# MOSFET_Board.net
KiCad netlist of a schematic drawn in EAGLE
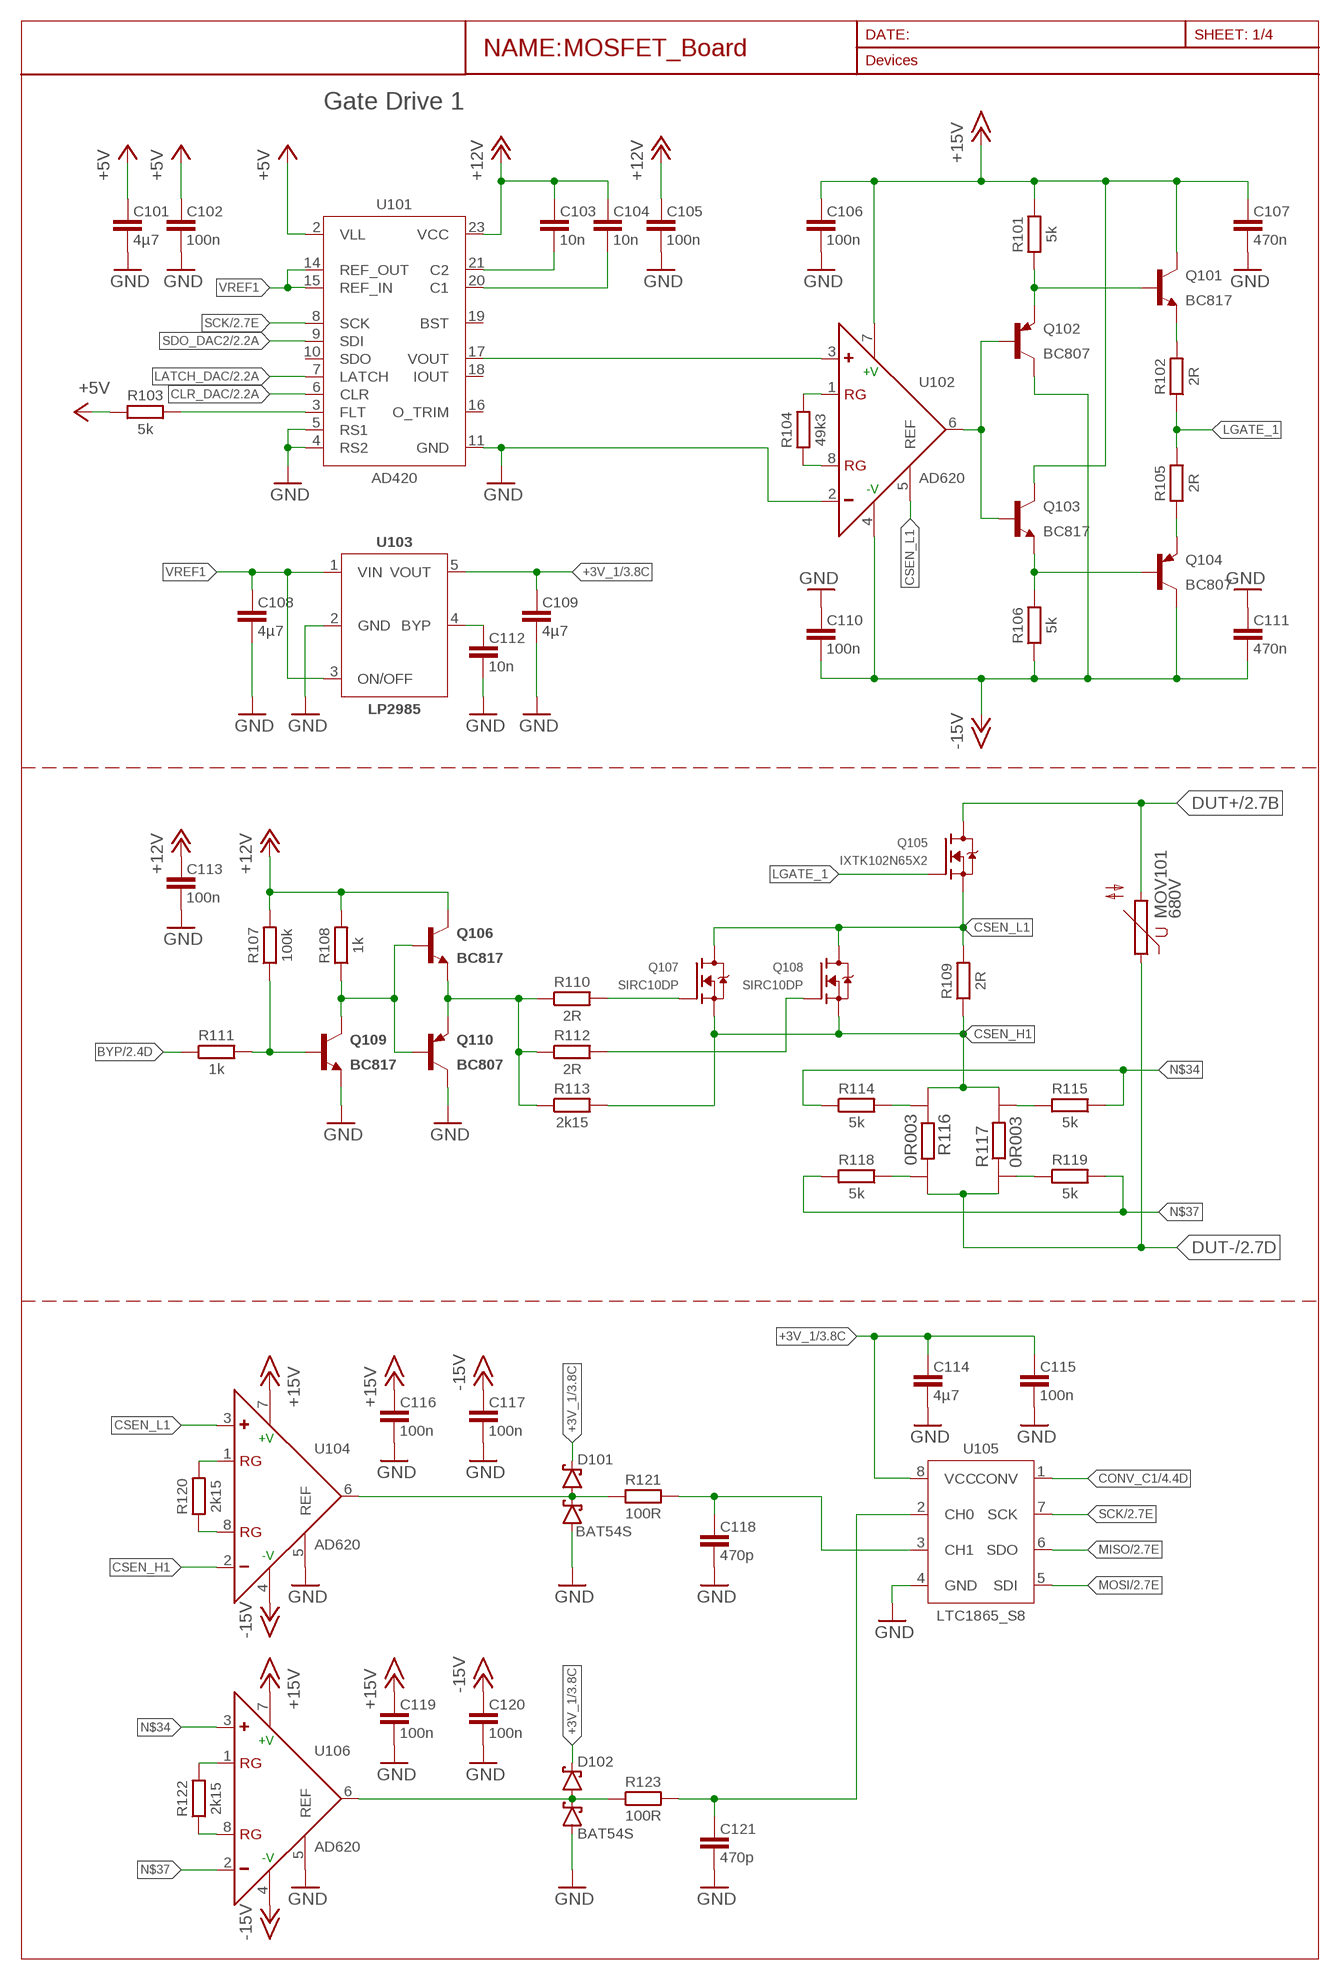
[diagram p0: schematic, sheet 1]
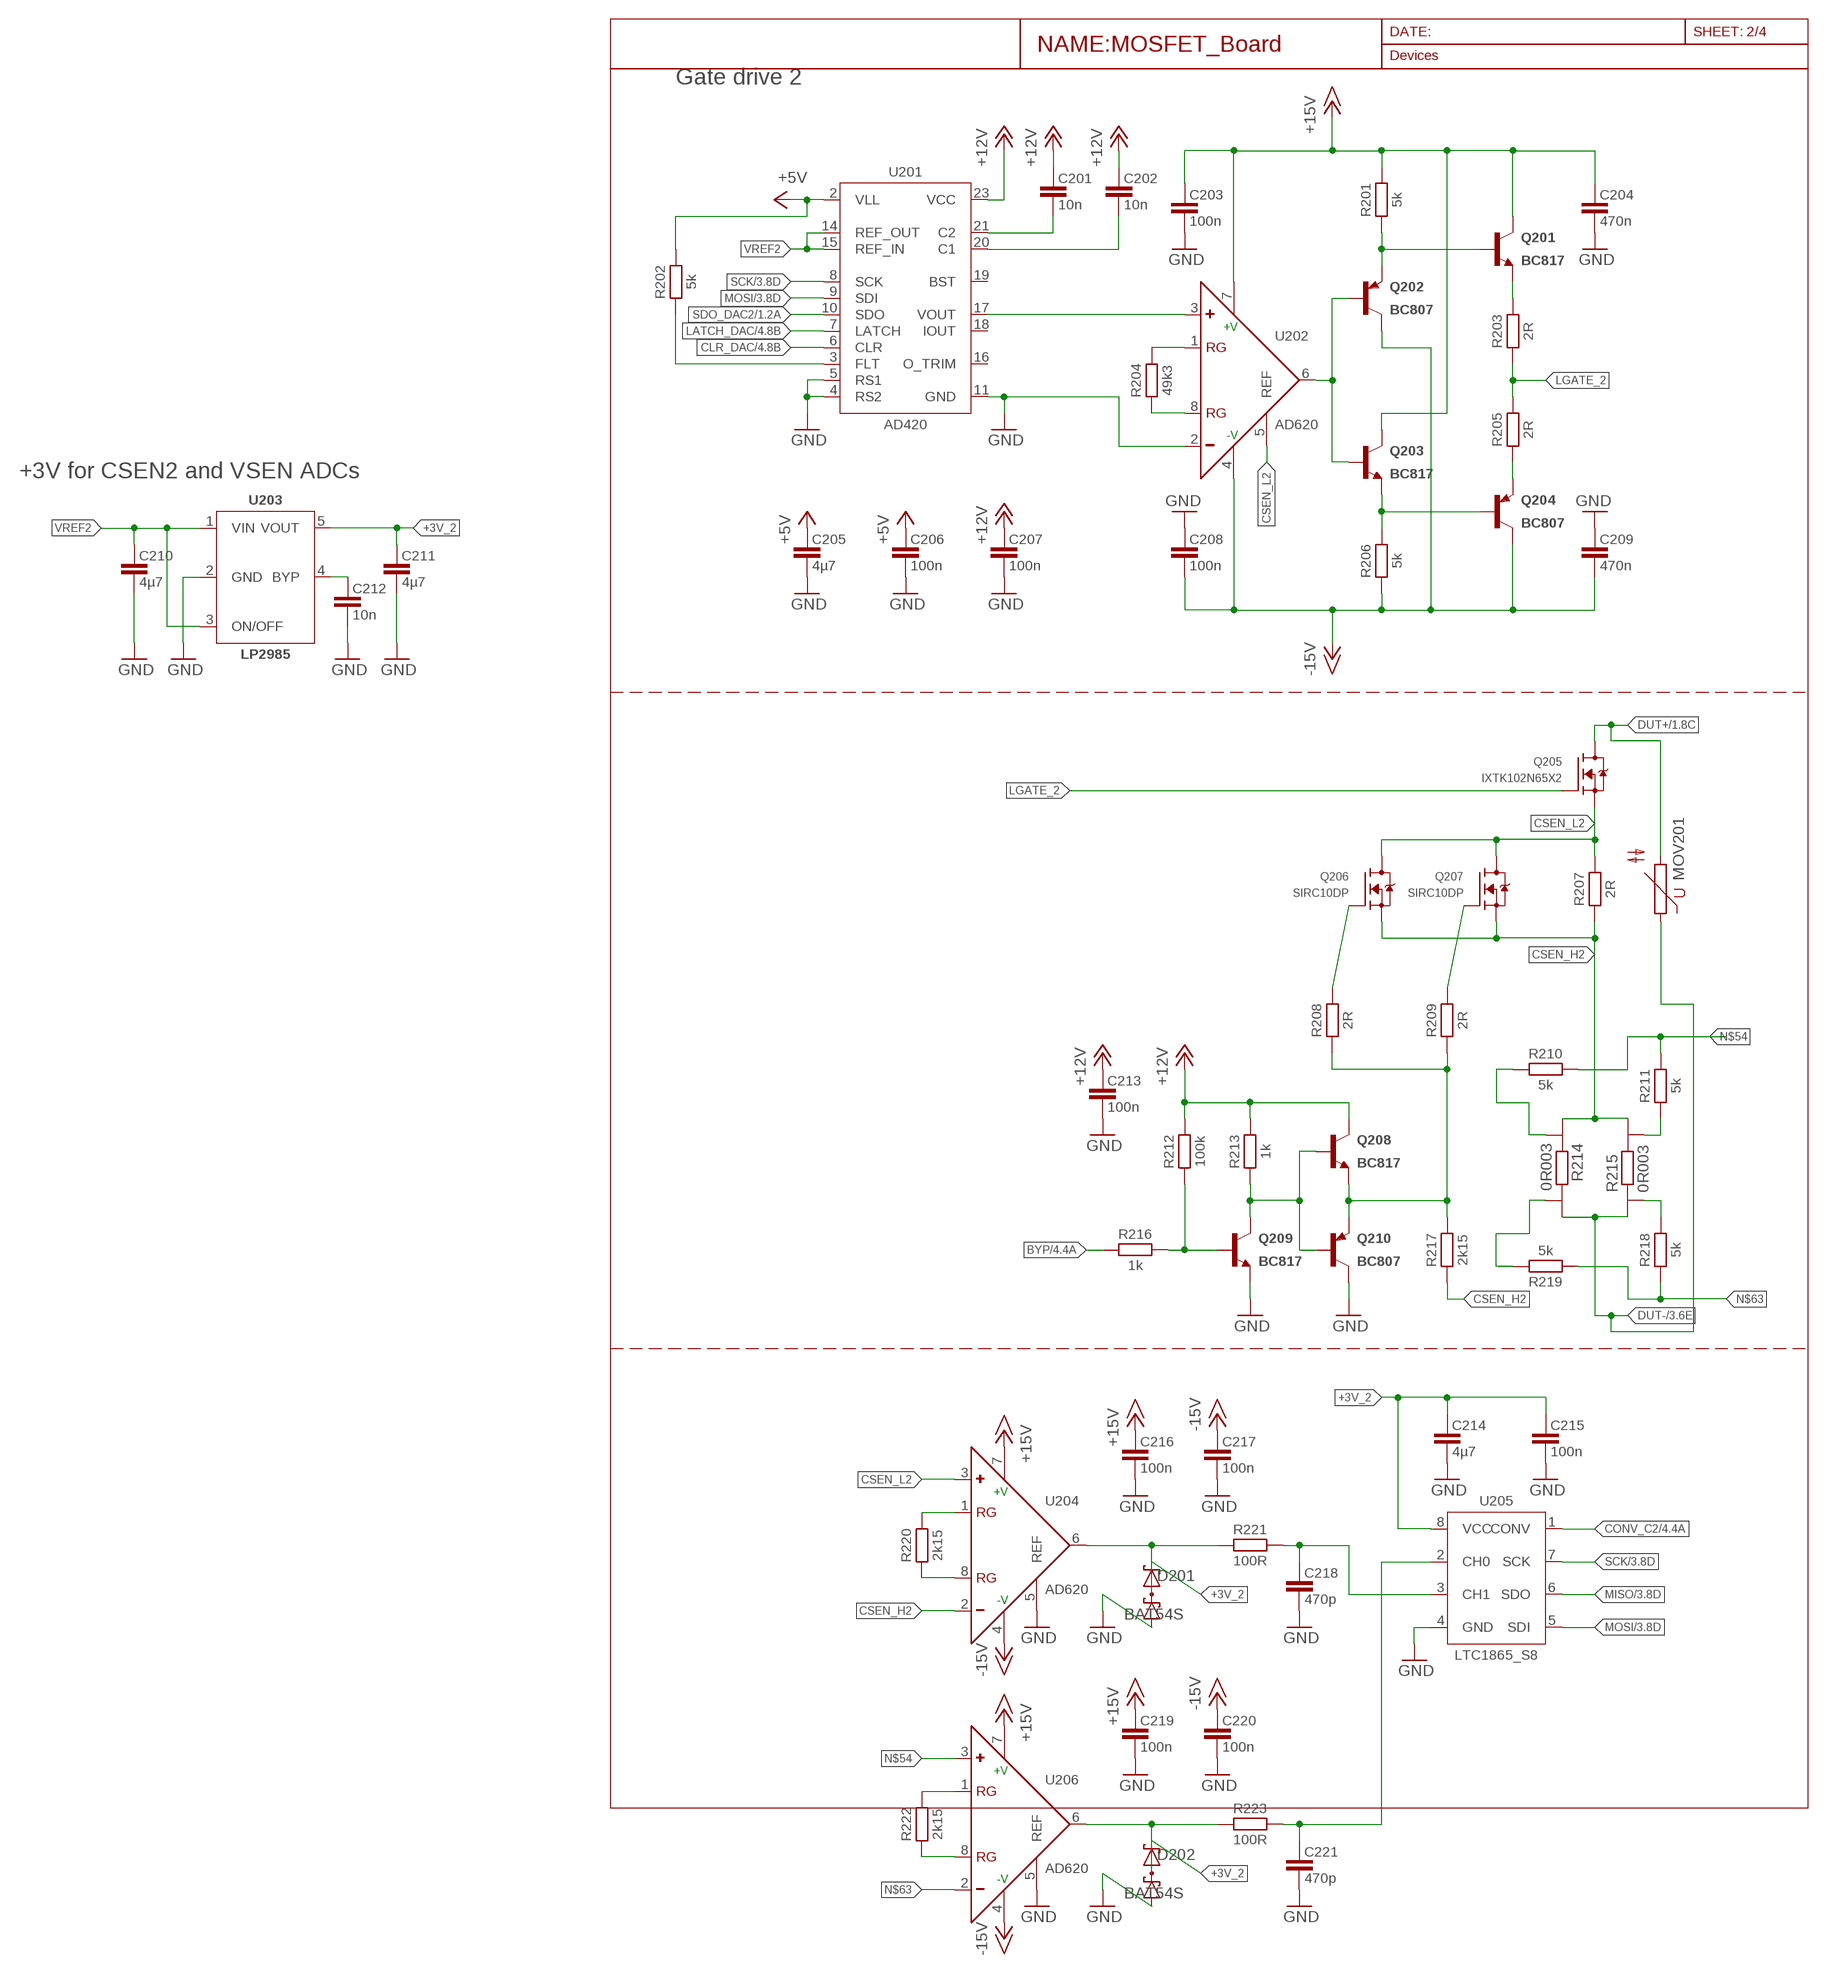
[diagram p1: schematic, sheet 2]
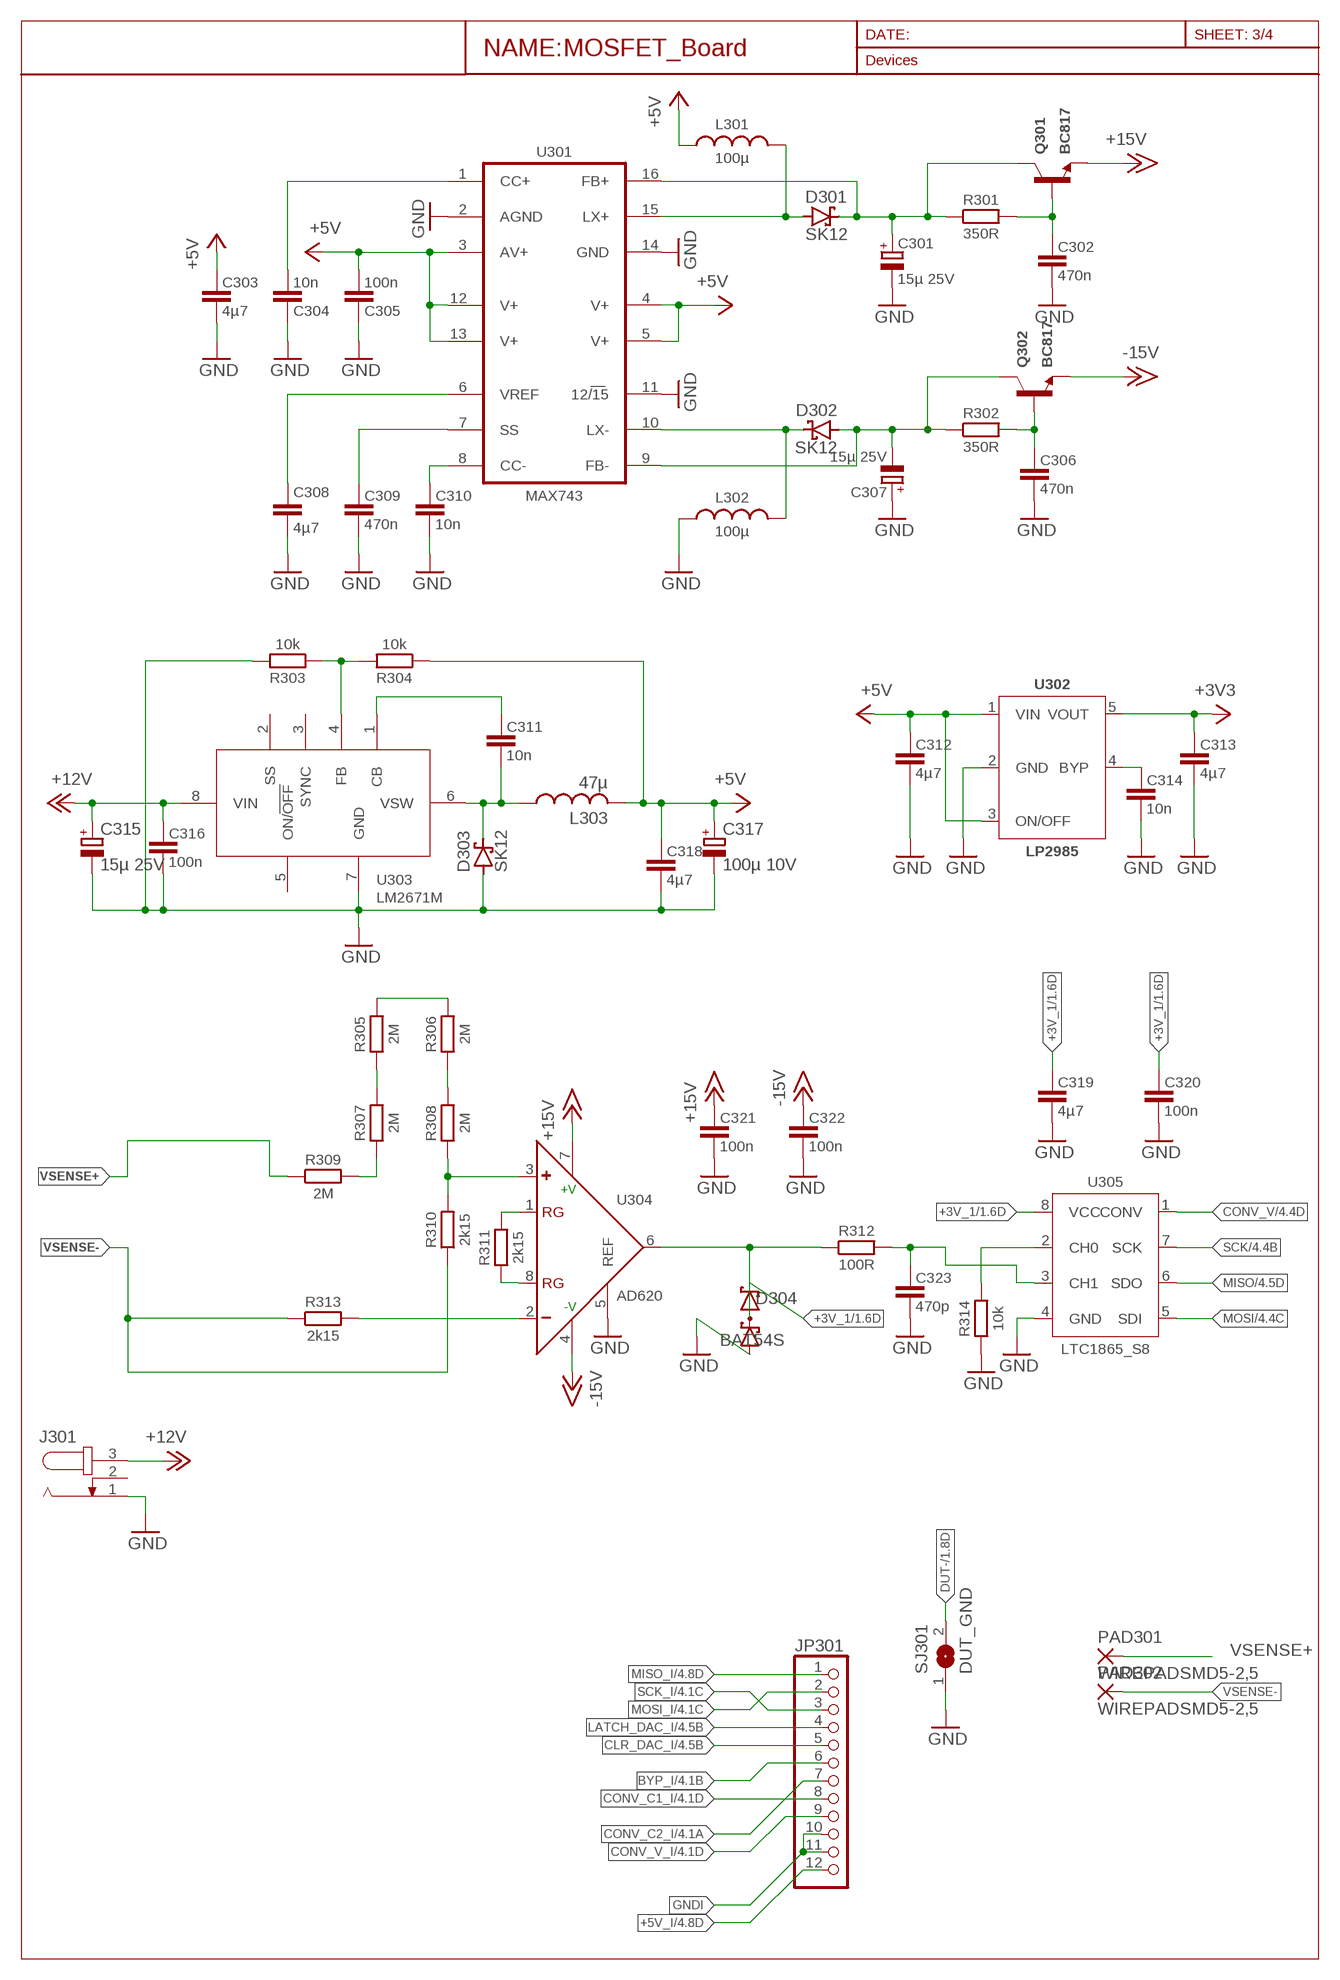
[diagram p2: schematic, sheet 3]
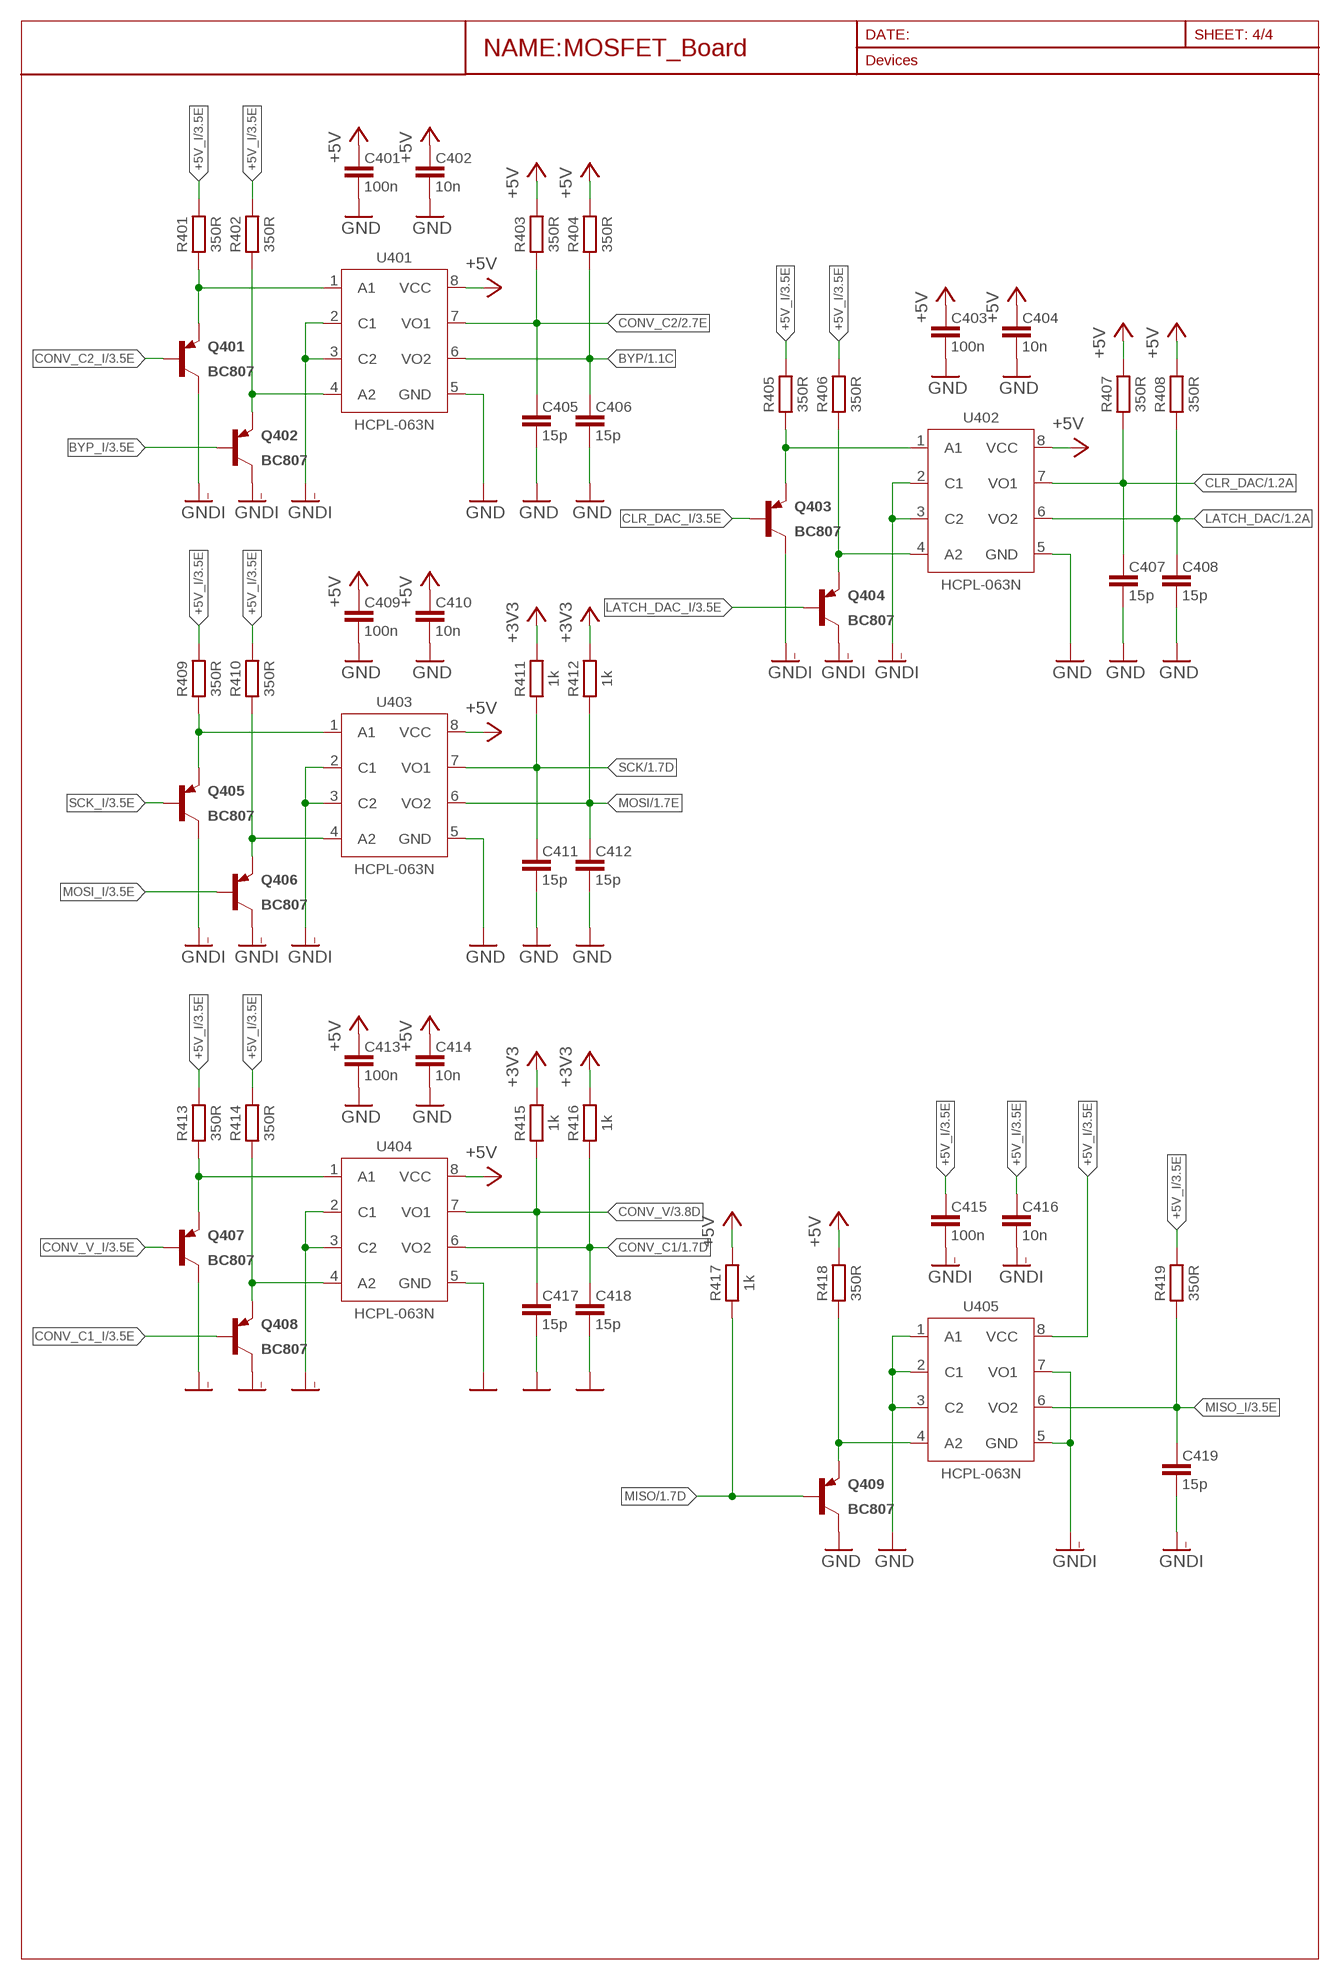
[diagram p3: schematic, sheet 4]

(export (version "E")
  (design (tool "Eeschema 10.0.6"))
  (components
    (comp (ref "C201")
      (value "10n")
      (footprint "eagle-import:CAPC1508X45")
      (libsource (lib "eagle-import") (part "CAP-1608"))
    )
    (comp (ref "C202")
      (value "10n")
      (footprint "eagle-import:CAPC1508X45")
      (libsource (lib "eagle-import") (part "CAP-1608"))
    )
    (comp (ref "C203")
      (value "100n")
      (footprint "eagle-import:CAPC1508X45")
      (libsource (lib "eagle-import") (part "CAP-1608"))
    )
    (comp (ref "C204")
      (value "470n")
      (footprint "eagle-import:CAPC1508X45")
      (libsource (lib "eagle-import") (part "CAP-1608"))
    )
    (comp (ref "C205")
      (value "4µ7")
      (footprint "eagle-import:CAPC3216X135")
      (libsource (lib "eagle-import") (part "CAP-3216"))
    )
    (comp (ref "C206")
      (value "100n")
      (footprint "eagle-import:CAPC1508X45")
      (libsource (lib "eagle-import") (part "CAP-1608"))
    )
    (comp (ref "C207")
      (value "100n")
      (footprint "eagle-import:CAPC1508X45")
      (libsource (lib "eagle-import") (part "CAP-1608"))
    )
    (comp (ref "C208")
      (value "100n")
      (footprint "eagle-import:CAPC1508X45")
      (libsource (lib "eagle-import") (part "CAP-1608"))
    )
    (comp (ref "C209")
      (value "470n")
      (footprint "eagle-import:CAPC1508X45")
      (libsource (lib "eagle-import") (part "CAP-1608"))
    )
    (comp (ref "C210")
      (value "4µ7")
      (footprint "eagle-import:CAPC3216X135")
      (libsource (lib "eagle-import") (part "CAP-3216"))
    )
    (comp (ref "C211")
      (value "4µ7")
      (footprint "eagle-import:CAPC3216X135")
      (libsource (lib "eagle-import") (part "CAP-3216"))
    )
    (comp (ref "C212")
      (value "10n")
      (footprint "eagle-import:CAPC1508X45")
      (libsource (lib "eagle-import") (part "CAP-1608"))
    )
    (comp (ref "C213")
      (value "100n")
      (footprint "eagle-import:CAPC1508X45")
      (libsource (lib "eagle-import") (part "CAP-1608"))
    )
    (comp (ref "C214")
      (value "4µ7")
      (footprint "eagle-import:CAPC3216X135")
      (libsource (lib "eagle-import") (part "CAP-3216"))
    )
    (comp (ref "C215")
      (value "100n")
      (footprint "eagle-import:CAPC1508X45")
      (libsource (lib "eagle-import") (part "CAP-1608"))
    )
    (comp (ref "C216")
      (value "100n")
      (footprint "eagle-import:CAPC1508X45")
      (libsource (lib "eagle-import") (part "CAP-1608"))
    )
    (comp (ref "C217")
      (value "100n")
      (footprint "eagle-import:CAPC1508X45")
      (libsource (lib "eagle-import") (part "CAP-1608"))
    )
    (comp (ref "C218")
      (value "470p")
      (footprint "eagle-import:CAPC1508X45")
      (libsource (lib "eagle-import") (part "CAP-1608"))
    )
    (comp (ref "C219")
      (value "100n")
      (footprint "eagle-import:CAPC1508X45")
      (libsource (lib "eagle-import") (part "CAP-1608"))
    )
    (comp (ref "C220")
      (value "100n")
      (footprint "eagle-import:CAPC1508X45")
      (libsource (lib "eagle-import") (part "CAP-1608"))
    )
    (comp (ref "C221")
      (value "470p")
      (footprint "eagle-import:CAPC1508X45")
      (libsource (lib "eagle-import") (part "CAP-1608"))
    )
    (comp (ref "D201")
      (value "BAT54S")
      (footprint "eagle-import:SOT95P230X110-3")
      (libsource (lib "eagle-import") (part "BAT54S"))
    )
    (comp (ref "D202")
      (value "BAT54S")
      (footprint "eagle-import:SOT95P230X110-3")
      (libsource (lib "eagle-import") (part "BAT54S"))
    )
    (comp (ref "MOV201")
      (value "MOV-14X7.4")
      (footprint "eagle-import:S14K680")
      (libsource (lib "eagle-import") (part "MOV-14X7.4"))
    )
    (comp (ref "Q201")
      (value "BC817")
      (footprint "eagle-import:SOT95P240X110-3")
      (libsource (lib "eagle-import") (part "BC817"))
    )
    (comp (ref "Q202")
      (value "BC807")
      (footprint "eagle-import:SOT95P240X110-3")
      (libsource (lib "eagle-import") (part "BC807"))
    )
    (comp (ref "Q203")
      (value "BC817")
      (footprint "eagle-import:SOT95P240X110-3")
      (libsource (lib "eagle-import") (part "BC817"))
    )
    (comp (ref "Q204")
      (value "BC807")
      (footprint "eagle-import:SOT95P240X110-3")
      (libsource (lib "eagle-import") (part "BC807"))
    )
    (comp (ref "Q205")
      (value "IXTK102N65X2")
      (footprint "eagle-import:TO-264P-V")
      (libsource (lib "eagle-import") (part "IXTK102N65X2"))
    )
    (comp (ref "Q206")
      (value "SIRC10DP")
      (footprint "eagle-import:POWERPAK-SO-8")
      (libsource (lib "eagle-import") (part "SIRC10DP"))
    )
    (comp (ref "Q207")
      (value "SIRC10DP")
      (footprint "eagle-import:POWERPAK-SO-8")
      (libsource (lib "eagle-import") (part "SIRC10DP"))
    )
    (comp (ref "Q208")
      (value "BC817")
      (footprint "eagle-import:SOT95P240X110-3")
      (libsource (lib "eagle-import") (part "BC817"))
    )
    (comp (ref "Q209")
      (value "BC817")
      (footprint "eagle-import:SOT95P240X110-3")
      (libsource (lib "eagle-import") (part "BC817"))
    )
    (comp (ref "Q210")
      (value "BC807")
      (footprint "eagle-import:SOT95P240X110-3")
      (libsource (lib "eagle-import") (part "BC807"))
    )
    (comp (ref "R201")
      (value "5k")
      (footprint "eagle-import:RESC1608X70")
      (libsource (lib "eagle-import") (part "R-EU-1608"))
    )
    (comp (ref "R202")
      (value "5k")
      (footprint "eagle-import:RESC1608X70")
      (libsource (lib "eagle-import") (part "R-EU-1608"))
    )
    (comp (ref "R203")
      (value "2R")
      (footprint "eagle-import:RESC3216X71")
      (libsource (lib "eagle-import") (part "R-EU-3216"))
    )
    (comp (ref "R204")
      (value "49k3")
      (footprint "eagle-import:RESC1608X70")
      (libsource (lib "eagle-import") (part "R-EU-1608"))
    )
    (comp (ref "R205")
      (value "2R")
      (footprint "eagle-import:RESC3216X71")
      (libsource (lib "eagle-import") (part "R-EU-3216"))
    )
    (comp (ref "R206")
      (value "5k")
      (footprint "eagle-import:RESC1608X70")
      (libsource (lib "eagle-import") (part "R-EU-1608"))
    )
    (comp (ref "R207")
      (value "2R")
      (footprint "eagle-import:RESC3216X71")
      (libsource (lib "eagle-import") (part "R-EU-3216"))
    )
    (comp (ref "R208")
      (value "2R")
      (footprint "eagle-import:RESC3216X71")
      (libsource (lib "eagle-import") (part "R-EU-3216"))
    )
    (comp (ref "R209")
      (value "2R")
      (footprint "eagle-import:RESC3216X71")
      (libsource (lib "eagle-import") (part "R-EU-3216"))
    )
    (comp (ref "R210")
      (value "5k")
      (footprint "eagle-import:RESC1608X70")
      (libsource (lib "eagle-import") (part "R-EU-1608"))
    )
    (comp (ref "R211")
      (value "5k")
      (footprint "eagle-import:RESC1608X70")
      (libsource (lib "eagle-import") (part "R-EU-1608"))
    )
    (comp (ref "R212")
      (value "100k")
      (footprint "eagle-import:RESC1608X70")
      (libsource (lib "eagle-import") (part "R-EU-1608"))
    )
    (comp (ref "R213")
      (value "1k")
      (footprint "eagle-import:RESC1608X70")
      (libsource (lib "eagle-import") (part "R-EU-1608"))
    )
    (comp (ref "R214")
      (value "0R003")
      (footprint "eagle-import:WSL3637_0.01")
      (libsource (lib "eagle-import") (part "WSL3637_0.01"))
    )
    (comp (ref "R215")
      (value "0R003")
      (footprint "eagle-import:WSL3637_0.01")
      (libsource (lib "eagle-import") (part "WSL3637_0.01"))
    )
    (comp (ref "R216")
      (value "1k")
      (footprint "eagle-import:RESC1608X70")
      (libsource (lib "eagle-import") (part "R-EU-1608"))
    )
    (comp (ref "R217")
      (value "2k15")
      (footprint "eagle-import:RESC2012X65")
      (libsource (lib "eagle-import") (part "R-EU-2012"))
    )
    (comp (ref "R218")
      (value "5k")
      (footprint "eagle-import:RESC1608X70")
      (libsource (lib "eagle-import") (part "R-EU-1608"))
    )
    (comp (ref "R219")
      (value "5k")
      (footprint "eagle-import:RESC1608X70")
      (libsource (lib "eagle-import") (part "R-EU-1608"))
    )
    (comp (ref "R220")
      (value "2k15")
      (footprint "eagle-import:RESC2012X65")
      (libsource (lib "eagle-import") (part "R-EU-2012"))
    )
    (comp (ref "R221")
      (value "100R")
      (footprint "eagle-import:RESC1608X70")
      (libsource (lib "eagle-import") (part "R-EU-1608"))
    )
    (comp (ref "R222")
      (value "2k15")
      (footprint "eagle-import:RESC2012X65")
      (libsource (lib "eagle-import") (part "R-EU-2012"))
    )
    (comp (ref "R223")
      (value "100R")
      (footprint "eagle-import:RESC1608X70")
      (libsource (lib "eagle-import") (part "R-EU-1608"))
    )
    (comp (ref "U201")
      (value "AD420")
      (footprint "eagle-import:SOIC127P1032X265-24")
      (libsource (lib "eagle-import") (part "AD420AR"))
    )
    (comp (ref "U202")
      (value "AD620")
      (footprint "eagle-import:SOIC127P599X175-8")
      (libsource (lib "eagle-import") (part "AD620R-8"))
    )
    (comp (ref "U203")
      (value "LP2985")
      (footprint "eagle-import:SOT95P280X145-5")
      (libsource (lib "eagle-import") (part "LP2985"))
    )
    (comp (ref "U204")
      (value "AD620")
      (footprint "eagle-import:SOIC127P599X175-8")
      (libsource (lib "eagle-import") (part "AD620R-8"))
    )
    (comp (ref "U205")
      (value "LTC1865_S8")
      (footprint "eagle-import:SOIC127P599X175-8")
      (libsource (lib "eagle-import") (part "LTC1865_S8"))
    )
    (comp (ref "U206")
      (value "AD620")
      (footprint "eagle-import:SOIC127P599X175-8")
      (libsource (lib "eagle-import") (part "AD620R-8"))
    )
    (comp (ref "C101")
      (value "4µ7")
      (footprint "eagle-import:CAPC3216X135")
      (libsource (lib "eagle-import") (part "CAP-3216"))
    )
    (comp (ref "C102")
      (value "100n")
      (footprint "eagle-import:CAPC1508X45")
      (libsource (lib "eagle-import") (part "CAP-1608"))
    )
    (comp (ref "C103")
      (value "10n")
      (footprint "eagle-import:CAPC1508X45")
      (libsource (lib "eagle-import") (part "CAP-1608"))
    )
    (comp (ref "C104")
      (value "10n")
      (footprint "eagle-import:CAPC1508X45")
      (libsource (lib "eagle-import") (part "CAP-1608"))
    )
    (comp (ref "C105")
      (value "100n")
      (footprint "eagle-import:CAPC1508X45")
      (libsource (lib "eagle-import") (part "CAP-1608"))
    )
    (comp (ref "C106")
      (value "100n")
      (footprint "eagle-import:CAPC1508X45")
      (libsource (lib "eagle-import") (part "CAP-1608"))
    )
    (comp (ref "C107")
      (value "470n")
      (footprint "eagle-import:CAPC1508X45")
      (libsource (lib "eagle-import") (part "CAP-1608"))
    )
    (comp (ref "C108")
      (value "4µ7")
      (footprint "eagle-import:CAPC3216X135")
      (libsource (lib "eagle-import") (part "CAP-3216"))
    )
    (comp (ref "C109")
      (value "4µ7")
      (footprint "eagle-import:CAPC3216X135")
      (libsource (lib "eagle-import") (part "CAP-3216"))
    )
    (comp (ref "C110")
      (value "100n")
      (footprint "eagle-import:CAPC1508X45")
      (libsource (lib "eagle-import") (part "CAP-1608"))
    )
    (comp (ref "C111")
      (value "470n")
      (footprint "eagle-import:CAPC1508X45")
      (libsource (lib "eagle-import") (part "CAP-1608"))
    )
    (comp (ref "C112")
      (value "10n")
      (footprint "eagle-import:CAPC1508X45")
      (libsource (lib "eagle-import") (part "CAP-1608"))
    )
    (comp (ref "C113")
      (value "100n")
      (footprint "eagle-import:CAPC1508X45")
      (libsource (lib "eagle-import") (part "CAP-1608"))
    )
    (comp (ref "C114")
      (value "4µ7")
      (footprint "eagle-import:CAPC3216X135")
      (libsource (lib "eagle-import") (part "CAP-3216"))
    )
    (comp (ref "C115")
      (value "100n")
      (footprint "eagle-import:CAPC1508X45")
      (libsource (lib "eagle-import") (part "CAP-1608"))
    )
    (comp (ref "C116")
      (value "100n")
      (footprint "eagle-import:CAPC1508X45")
      (libsource (lib "eagle-import") (part "CAP-1608"))
    )
    (comp (ref "C117")
      (value "100n")
      (footprint "eagle-import:CAPC1508X45")
      (libsource (lib "eagle-import") (part "CAP-1608"))
    )
    (comp (ref "C118")
      (value "470p")
      (footprint "eagle-import:CAPC1508X45")
      (libsource (lib "eagle-import") (part "CAP-1608"))
    )
    (comp (ref "C119")
      (value "100n")
      (footprint "eagle-import:CAPC1508X45")
      (libsource (lib "eagle-import") (part "CAP-1608"))
    )
    (comp (ref "C120")
      (value "100n")
      (footprint "eagle-import:CAPC1508X45")
      (libsource (lib "eagle-import") (part "CAP-1608"))
    )
    (comp (ref "C121")
      (value "470p")
      (footprint "eagle-import:CAPC1508X45")
      (libsource (lib "eagle-import") (part "CAP-1608"))
    )
    (comp (ref "D101")
      (value "BAT54S")
      (footprint "eagle-import:SOT95P230X110-3")
      (libsource (lib "eagle-import") (part "BAT54S"))
    )
    (comp (ref "D102")
      (value "BAT54S")
      (footprint "eagle-import:SOT95P230X110-3")
      (libsource (lib "eagle-import") (part "BAT54S"))
    )
    (comp (ref "MOV101")
      (value "680V")
      (footprint "eagle-import:S14K680")
      (libsource (lib "eagle-import") (part "MOV-14X7.4"))
    )
    (comp (ref "Q101")
      (value "BC817")
      (footprint "eagle-import:SOT95P240X110-3")
      (libsource (lib "eagle-import") (part "BC817"))
    )
    (comp (ref "Q102")
      (value "BC807")
      (footprint "eagle-import:SOT95P240X110-3")
      (libsource (lib "eagle-import") (part "BC807"))
    )
    (comp (ref "Q103")
      (value "BC817")
      (footprint "eagle-import:SOT95P240X110-3")
      (libsource (lib "eagle-import") (part "BC817"))
    )
    (comp (ref "Q104")
      (value "BC807")
      (footprint "eagle-import:SOT95P240X110-3")
      (libsource (lib "eagle-import") (part "BC807"))
    )
    (comp (ref "Q105")
      (value "IXTK102N65X2")
      (footprint "eagle-import:TO-264P-V")
      (libsource (lib "eagle-import") (part "IXTK102N65X2"))
    )
    (comp (ref "Q106")
      (value "BC817")
      (footprint "eagle-import:SOT95P240X110-3")
      (libsource (lib "eagle-import") (part "BC817"))
    )
    (comp (ref "Q107")
      (value "SIRC10DP")
      (footprint "eagle-import:POWERPAK-SO-8")
      (libsource (lib "eagle-import") (part "SIRC10DP"))
    )
    (comp (ref "Q108")
      (value "SIRC10DP")
      (footprint "eagle-import:POWERPAK-SO-8")
      (libsource (lib "eagle-import") (part "SIRC10DP"))
    )
    (comp (ref "Q109")
      (value "BC817")
      (footprint "eagle-import:SOT95P240X110-3")
      (libsource (lib "eagle-import") (part "BC817"))
    )
    (comp (ref "Q110")
      (value "BC807")
      (footprint "eagle-import:SOT95P240X110-3")
      (libsource (lib "eagle-import") (part "BC807"))
    )
    (comp (ref "R101")
      (value "5k")
      (footprint "eagle-import:RESC1608X70")
      (libsource (lib "eagle-import") (part "R-EU-1608"))
    )
    (comp (ref "R102")
      (value "2R")
      (footprint "eagle-import:RESC3216X71")
      (libsource (lib "eagle-import") (part "R-EU-3216"))
    )
    (comp (ref "R103")
      (value "5k")
      (footprint "eagle-import:RESC1608X70")
      (libsource (lib "eagle-import") (part "R-EU-1608"))
    )
    (comp (ref "R104")
      (value "49k3")
      (footprint "eagle-import:RESC1608X70")
      (libsource (lib "eagle-import") (part "R-EU-1608"))
    )
    (comp (ref "R105")
      (value "2R")
      (footprint "eagle-import:RESC3216X71")
      (libsource (lib "eagle-import") (part "R-EU-3216"))
    )
    (comp (ref "R106")
      (value "5k")
      (footprint "eagle-import:RESC1608X70")
      (libsource (lib "eagle-import") (part "R-EU-1608"))
    )
    (comp (ref "R107")
      (value "100k")
      (footprint "eagle-import:RESC1608X70")
      (libsource (lib "eagle-import") (part "R-EU-1608"))
    )
    (comp (ref "R108")
      (value "1k")
      (footprint "eagle-import:RESC1608X70")
      (libsource (lib "eagle-import") (part "R-EU-1608"))
    )
    (comp (ref "R109")
      (value "2R")
      (footprint "eagle-import:RESC3216X71")
      (libsource (lib "eagle-import") (part "R-EU-3216"))
    )
    (comp (ref "R110")
      (value "2R")
      (footprint "eagle-import:RESC3216X71")
      (libsource (lib "eagle-import") (part "R-EU-3216"))
    )
    (comp (ref "R111")
      (value "1k")
      (footprint "eagle-import:RESC1608X70")
      (libsource (lib "eagle-import") (part "R-EU-1608"))
    )
    (comp (ref "R112")
      (value "2R")
      (footprint "eagle-import:RESC3216X71")
      (libsource (lib "eagle-import") (part "R-EU-3216"))
    )
    (comp (ref "R113")
      (value "2k15")
      (footprint "eagle-import:RESC2012X65")
      (libsource (lib "eagle-import") (part "R-EU-2012"))
    )
    (comp (ref "R114")
      (value "5k")
      (footprint "eagle-import:RESC1608X70")
      (libsource (lib "eagle-import") (part "R-EU-1608"))
    )
    (comp (ref "R115")
      (value "5k")
      (footprint "eagle-import:RESC1608X70")
      (libsource (lib "eagle-import") (part "R-EU-1608"))
    )
    (comp (ref "R116")
      (value "0R003")
      (footprint "eagle-import:WSL3637_0.01")
      (libsource (lib "eagle-import") (part "WSL3637_0.01"))
    )
    (comp (ref "R117")
      (value "0R003")
      (footprint "eagle-import:WSL3637_0.01")
      (libsource (lib "eagle-import") (part "WSL3637_0.01"))
    )
    (comp (ref "R118")
      (value "5k")
      (footprint "eagle-import:RESC1608X70")
      (libsource (lib "eagle-import") (part "R-EU-1608"))
    )
    (comp (ref "R119")
      (value "5k")
      (footprint "eagle-import:RESC1608X70")
      (libsource (lib "eagle-import") (part "R-EU-1608"))
    )
    (comp (ref "R120")
      (value "2k15")
      (footprint "eagle-import:RESC2012X65")
      (libsource (lib "eagle-import") (part "R-EU-2012"))
    )
    (comp (ref "R121")
      (value "100R")
      (footprint "eagle-import:RESC1608X70")
      (libsource (lib "eagle-import") (part "R-EU-1608"))
    )
    (comp (ref "R122")
      (value "2k15")
      (footprint "eagle-import:RESC2012X65")
      (libsource (lib "eagle-import") (part "R-EU-2012"))
    )
    (comp (ref "R123")
      (value "100R")
      (footprint "eagle-import:RESC1608X70")
      (libsource (lib "eagle-import") (part "R-EU-1608"))
    )
    (comp (ref "U101")
      (value "AD420")
      (footprint "eagle-import:SOIC127P1032X265-24")
      (libsource (lib "eagle-import") (part "AD420AR"))
    )
    (comp (ref "U102")
      (value "AD620")
      (footprint "eagle-import:SOIC127P599X175-8")
      (libsource (lib "eagle-import") (part "AD620R-8"))
    )
    (comp (ref "U103")
      (value "LP2985")
      (footprint "eagle-import:SOT95P280X145-5")
      (libsource (lib "eagle-import") (part "LP2985"))
    )
    (comp (ref "U104")
      (value "AD620")
      (footprint "eagle-import:SOIC127P599X175-8")
      (libsource (lib "eagle-import") (part "AD620R-8"))
    )
    (comp (ref "U105")
      (value "LTC1865_S8")
      (footprint "eagle-import:SOIC127P599X175-8")
      (libsource (lib "eagle-import") (part "LTC1865_S8"))
    )
    (comp (ref "U106")
      (value "AD620")
      (footprint "eagle-import:SOIC127P599X175-8")
      (libsource (lib "eagle-import") (part "AD620R-8"))
    )
    (comp (ref "C401")
      (value "100n")
      (footprint "eagle-import:CAPC1508X45")
      (libsource (lib "eagle-import") (part "CAP-1608"))
    )
    (comp (ref "C402")
      (value "10n")
      (footprint "eagle-import:CAPC1508X45")
      (libsource (lib "eagle-import") (part "CAP-1608"))
    )
    (comp (ref "C403")
      (value "100n")
      (footprint "eagle-import:CAPC1508X45")
      (libsource (lib "eagle-import") (part "CAP-1608"))
    )
    (comp (ref "C404")
      (value "10n")
      (footprint "eagle-import:CAPC1508X45")
      (libsource (lib "eagle-import") (part "CAP-1608"))
    )
    (comp (ref "C405")
      (value "15p")
      (footprint "eagle-import:CAPC1508X45")
      (libsource (lib "eagle-import") (part "CAP-1608"))
    )
    (comp (ref "C406")
      (value "15p")
      (footprint "eagle-import:CAPC1508X45")
      (libsource (lib "eagle-import") (part "CAP-1608"))
    )
    (comp (ref "C407")
      (value "15p")
      (footprint "eagle-import:CAPC1508X45")
      (libsource (lib "eagle-import") (part "CAP-1608"))
    )
    (comp (ref "C408")
      (value "15p")
      (footprint "eagle-import:CAPC1508X45")
      (libsource (lib "eagle-import") (part "CAP-1608"))
    )
    (comp (ref "C409")
      (value "100n")
      (footprint "eagle-import:CAPC1508X45")
      (libsource (lib "eagle-import") (part "CAP-1608"))
    )
    (comp (ref "C410")
      (value "10n")
      (footprint "eagle-import:CAPC1508X45")
      (libsource (lib "eagle-import") (part "CAP-1608"))
    )
    (comp (ref "C411")
      (value "15p")
      (footprint "eagle-import:CAPC1508X45")
      (libsource (lib "eagle-import") (part "CAP-1608"))
    )
    (comp (ref "C412")
      (value "15p")
      (footprint "eagle-import:CAPC1508X45")
      (libsource (lib "eagle-import") (part "CAP-1608"))
    )
    (comp (ref "C413")
      (value "100n")
      (footprint "eagle-import:CAPC1508X45")
      (libsource (lib "eagle-import") (part "CAP-1608"))
    )
    (comp (ref "C414")
      (value "10n")
      (footprint "eagle-import:CAPC1508X45")
      (libsource (lib "eagle-import") (part "CAP-1608"))
    )
    (comp (ref "C415")
      (value "100n")
      (footprint "eagle-import:CAPC1508X45")
      (libsource (lib "eagle-import") (part "CAP-1608"))
    )
    (comp (ref "C416")
      (value "10n")
      (footprint "eagle-import:CAPC1508X45")
      (libsource (lib "eagle-import") (part "CAP-1608"))
    )
    (comp (ref "C417")
      (value "15p")
      (footprint "eagle-import:CAPC1508X45")
      (libsource (lib "eagle-import") (part "CAP-1608"))
    )
    (comp (ref "C418")
      (value "15p")
      (footprint "eagle-import:CAPC1508X45")
      (libsource (lib "eagle-import") (part "CAP-1608"))
    )
    (comp (ref "C419")
      (value "15p")
      (footprint "eagle-import:CAPC1508X45")
      (libsource (lib "eagle-import") (part "CAP-1608"))
    )
    (comp (ref "Q401")
      (value "BC807")
      (footprint "eagle-import:SOT95P240X110-3")
      (libsource (lib "eagle-import") (part "BC807"))
    )
    (comp (ref "Q402")
      (value "BC807")
      (footprint "eagle-import:SOT95P240X110-3")
      (libsource (lib "eagle-import") (part "BC807"))
    )
    (comp (ref "Q403")
      (value "BC807")
      (footprint "eagle-import:SOT95P240X110-3")
      (libsource (lib "eagle-import") (part "BC807"))
    )
    (comp (ref "Q404")
      (value "BC807")
      (footprint "eagle-import:SOT95P240X110-3")
      (libsource (lib "eagle-import") (part "BC807"))
    )
    (comp (ref "Q405")
      (value "BC807")
      (footprint "eagle-import:SOT95P240X110-3")
      (libsource (lib "eagle-import") (part "BC807"))
    )
    (comp (ref "Q406")
      (value "BC807")
      (footprint "eagle-import:SOT95P240X110-3")
      (libsource (lib "eagle-import") (part "BC807"))
    )
    (comp (ref "Q407")
      (value "BC807")
      (footprint "eagle-import:SOT95P240X110-3")
      (libsource (lib "eagle-import") (part "BC807"))
    )
    (comp (ref "Q408")
      (value "BC807")
      (footprint "eagle-import:SOT95P240X110-3")
      (libsource (lib "eagle-import") (part "BC807"))
    )
    (comp (ref "Q409")
      (value "BC807")
      (footprint "eagle-import:SOT95P240X110-3")
      (libsource (lib "eagle-import") (part "BC807"))
    )
    (comp (ref "R401")
      (value "350R")
      (footprint "eagle-import:RESC1608X70")
      (libsource (lib "eagle-import") (part "R-EU-1608"))
    )
    (comp (ref "R402")
      (value "350R")
      (footprint "eagle-import:RESC1608X70")
      (libsource (lib "eagle-import") (part "R-EU-1608"))
    )
    (comp (ref "R403")
      (value "350R")
      (footprint "eagle-import:RESC1608X70")
      (libsource (lib "eagle-import") (part "R-EU-1608"))
    )
    (comp (ref "R404")
      (value "350R")
      (footprint "eagle-import:RESC1608X70")
      (libsource (lib "eagle-import") (part "R-EU-1608"))
    )
    (comp (ref "R405")
      (value "350R")
      (footprint "eagle-import:RESC1608X70")
      (libsource (lib "eagle-import") (part "R-EU-1608"))
    )
    (comp (ref "R406")
      (value "350R")
      (footprint "eagle-import:RESC1608X70")
      (libsource (lib "eagle-import") (part "R-EU-1608"))
    )
    (comp (ref "R407")
      (value "350R")
      (footprint "eagle-import:RESC1608X70")
      (libsource (lib "eagle-import") (part "R-EU-1608"))
    )
    (comp (ref "R408")
      (value "350R")
      (footprint "eagle-import:RESC1608X70")
      (libsource (lib "eagle-import") (part "R-EU-1608"))
    )
    (comp (ref "R409")
      (value "350R")
      (footprint "eagle-import:RESC1608X70")
      (libsource (lib "eagle-import") (part "R-EU-1608"))
    )
    (comp (ref "R410")
      (value "350R")
      (footprint "eagle-import:RESC1608X70")
      (libsource (lib "eagle-import") (part "R-EU-1608"))
    )
    (comp (ref "R411")
      (value "1k")
      (footprint "eagle-import:RESC1608X70")
      (libsource (lib "eagle-import") (part "R-EU-1608"))
    )
    (comp (ref "R412")
      (value "1k")
      (footprint "eagle-import:RESC1608X70")
      (libsource (lib "eagle-import") (part "R-EU-1608"))
    )
    (comp (ref "R413")
      (value "350R")
      (footprint "eagle-import:RESC1608X70")
      (libsource (lib "eagle-import") (part "R-EU-1608"))
    )
    (comp (ref "R414")
      (value "350R")
      (footprint "eagle-import:RESC1608X70")
      (libsource (lib "eagle-import") (part "R-EU-1608"))
    )
    (comp (ref "R415")
      (value "1k")
      (footprint "eagle-import:RESC1608X70")
      (libsource (lib "eagle-import") (part "R-EU-1608"))
    )
    (comp (ref "R416")
      (value "1k")
      (footprint "eagle-import:RESC1608X70")
      (libsource (lib "eagle-import") (part "R-EU-1608"))
    )
    (comp (ref "R417")
      (value "1k")
      (footprint "eagle-import:RESC1608X70")
      (libsource (lib "eagle-import") (part "R-EU-1608"))
    )
    (comp (ref "R418")
      (value "350R")
      (footprint "eagle-import:RESC1608X70")
      (libsource (lib "eagle-import") (part "R-EU-1608"))
    )
    (comp (ref "R419")
      (value "350R")
      (footprint "eagle-import:RESC1608X70")
      (libsource (lib "eagle-import") (part "R-EU-1608"))
    )
    (comp (ref "U401")
      (value "HCPL-063N")
      (footprint "eagle-import:SOIC127P599X175-8")
      (libsource (lib "eagle-import") (part "HCPL-063N"))
    )
    (comp (ref "U402")
      (value "HCPL-063N")
      (footprint "eagle-import:SOIC127P599X175-8")
      (libsource (lib "eagle-import") (part "HCPL-063N"))
    )
    (comp (ref "U403")
      (value "HCPL-063N")
      (footprint "eagle-import:SOIC127P599X175-8")
      (libsource (lib "eagle-import") (part "HCPL-063N"))
    )
    (comp (ref "U404")
      (value "HCPL-063N")
      (footprint "eagle-import:SOIC127P599X175-8")
      (libsource (lib "eagle-import") (part "HCPL-063N"))
    )
    (comp (ref "U405")
      (value "HCPL-063N")
      (footprint "eagle-import:SOIC127P599X175-8")
      (libsource (lib "eagle-import") (part "HCPL-063N"))
    )
    (comp (ref "C301")
      (value "15µ 25V")
      (footprint "eagle-import:CAPCP7343X310")
      (libsource (lib "eagle-import") (part "CAP-POL7343"))
    )
    (comp (ref "C302")
      (value "470n")
      (footprint "eagle-import:CAPC1508X45")
      (libsource (lib "eagle-import") (part "CAP-1608"))
    )
    (comp (ref "C303")
      (value "4µ7")
      (footprint "eagle-import:CAPC3216X135")
      (libsource (lib "eagle-import") (part "CAP-3216"))
    )
    (comp (ref "C304")
      (value "10n")
      (footprint "eagle-import:CAPC1508X45")
      (libsource (lib "eagle-import") (part "CAP-1608"))
    )
    (comp (ref "C305")
      (value "100n")
      (footprint "eagle-import:CAPC1508X45")
      (libsource (lib "eagle-import") (part "CAP-1608"))
    )
    (comp (ref "C306")
      (value "470n")
      (footprint "eagle-import:CAPC1508X45")
      (libsource (lib "eagle-import") (part "CAP-1608"))
    )
    (comp (ref "C307")
      (value "15µ 25V")
      (footprint "eagle-import:CAPCP7343X310")
      (libsource (lib "eagle-import") (part "CAP-POL7343"))
    )
    (comp (ref "C308")
      (value "4µ7")
      (footprint "eagle-import:CAPC3216X135")
      (libsource (lib "eagle-import") (part "CAP-3216"))
    )
    (comp (ref "C309")
      (value "470n")
      (footprint "eagle-import:CAPC1508X45")
      (libsource (lib "eagle-import") (part "CAP-1608"))
    )
    (comp (ref "C310")
      (value "10n")
      (footprint "eagle-import:CAPC1508X45")
      (libsource (lib "eagle-import") (part "CAP-1608"))
    )
    (comp (ref "C311")
      (value "10n")
      (footprint "eagle-import:CAPC1508X45")
      (libsource (lib "eagle-import") (part "CAP-1608"))
    )
    (comp (ref "C312")
      (value "4µ7")
      (footprint "eagle-import:CAPC3216X135")
      (libsource (lib "eagle-import") (part "CAP-3216"))
    )
    (comp (ref "C313")
      (value "4µ7")
      (footprint "eagle-import:CAPC3216X135")
      (libsource (lib "eagle-import") (part "CAP-3216"))
    )
    (comp (ref "C314")
      (value "10n")
      (footprint "eagle-import:CAPC1508X45")
      (libsource (lib "eagle-import") (part "CAP-1608"))
    )
    (comp (ref "C315")
      (value "15µ 25V")
      (footprint "eagle-import:CAPCP7343X310")
      (libsource (lib "eagle-import") (part "CAP-POL7343"))
    )
    (comp (ref "C316")
      (value "100n")
      (footprint "eagle-import:CAPC1508X45")
      (libsource (lib "eagle-import") (part "CAP-1608"))
    )
    (comp (ref "C317")
      (value "100µ 10V")
      (footprint "eagle-import:CAPCP7343X310")
      (libsource (lib "eagle-import") (part "CAP-POL7343"))
    )
    (comp (ref "C318")
      (value "4µ7")
      (footprint "eagle-import:CAPC3216X135")
      (libsource (lib "eagle-import") (part "CAP-3216"))
    )
    (comp (ref "C319")
      (value "4µ7")
      (footprint "eagle-import:CAPC3216X135")
      (libsource (lib "eagle-import") (part "CAP-3216"))
    )
    (comp (ref "C320")
      (value "100n")
      (footprint "eagle-import:CAPC1508X45")
      (libsource (lib "eagle-import") (part "CAP-1608"))
    )
    (comp (ref "C321")
      (value "100n")
      (footprint "eagle-import:CAPC1508X45")
      (libsource (lib "eagle-import") (part "CAP-1608"))
    )
    (comp (ref "C322")
      (value "100n")
      (footprint "eagle-import:CAPC1508X45")
      (libsource (lib "eagle-import") (part "CAP-1608"))
    )
    (comp (ref "C323")
      (value "470p")
      (footprint "eagle-import:CAPC1508X45")
      (libsource (lib "eagle-import") (part "CAP-1608"))
    )
    (comp (ref "D301")
      (value "SK12")
      (footprint "eagle-import:DIOM4336X262")
      (libsource (lib "eagle-import") (part "SK12"))
    )
    (comp (ref "D302")
      (value "SK12")
      (footprint "eagle-import:DIOM4336X262")
      (libsource (lib "eagle-import") (part "SK12"))
    )
    (comp (ref "D303")
      (value "SK12")
      (footprint "eagle-import:DIOM4336X262")
      (libsource (lib "eagle-import") (part "SK12"))
    )
    (comp (ref "D304")
      (value "BAT54S")
      (footprint "eagle-import:SOT95P230X110-3")
      (libsource (lib "eagle-import") (part "BAT54S"))
    )
    (comp (ref "J301")
      (value "JACK-PLUG-2.5")
      (footprint "eagle-import:SPC4078")
      (libsource (lib "eagle-import") (part "JACK-PLUG-2.5"))
    )
    (comp (ref "JP301")
      (value "PINHD-1X12")
      (footprint "eagle-import:1X12")
      (libsource (lib "eagle-import") (part "PINHD-1X12"))
    )
    (comp (ref "L301")
      (value "100µ")
      (footprint "eagle-import:SRN5040")
      (libsource (lib "eagle-import") (part "SRN5040"))
    )
    (comp (ref "L302")
      (value "100µ")
      (footprint "eagle-import:SRN5040")
      (libsource (lib "eagle-import") (part "SRN5040"))
    )
    (comp (ref "L303")
      (value "47µ")
      (footprint "eagle-import:SRN5040")
      (libsource (lib "eagle-import") (part "SRN5040"))
    )
    (comp (ref "PAD301")
      (value "WIREPADSMD5-2,5")
      (footprint "eagle-import:5-2,5")
      (libsource (lib "eagle-import") (part "WIREPADSMD5-2,5"))
    )
    (comp (ref "PAD302")
      (value "WIREPADSMD5-2,5")
      (footprint "eagle-import:5-2,5")
      (libsource (lib "eagle-import") (part "WIREPADSMD5-2,5"))
    )
    (comp (ref "Q301")
      (value "BC817")
      (footprint "eagle-import:SOT95P240X110-3")
      (libsource (lib "eagle-import") (part "BC817"))
    )
    (comp (ref "Q302")
      (value "BC817")
      (footprint "eagle-import:SOT95P240X110-3")
      (libsource (lib "eagle-import") (part "BC817"))
    )
    (comp (ref "R301")
      (value "350R")
      (footprint "eagle-import:RESC1608X70")
      (libsource (lib "eagle-import") (part "R-EU-1608"))
    )
    (comp (ref "R302")
      (value "350R")
      (footprint "eagle-import:RESC1608X70")
      (libsource (lib "eagle-import") (part "R-EU-1608"))
    )
    (comp (ref "R303")
      (value "10k")
      (footprint "eagle-import:RESC1608X70")
      (libsource (lib "eagle-import") (part "R-EU-1608"))
    )
    (comp (ref "R304")
      (value "10k")
      (footprint "eagle-import:RESC1608X70")
      (libsource (lib "eagle-import") (part "R-EU-1608"))
    )
    (comp (ref "R305")
      (value "2M")
      (footprint "eagle-import:RESC3216X71")
      (libsource (lib "eagle-import") (part "R-EU-3216"))
    )
    (comp (ref "R306")
      (value "2M")
      (footprint "eagle-import:RESC3216X71")
      (libsource (lib "eagle-import") (part "R-EU-3216"))
    )
    (comp (ref "R307")
      (value "2M")
      (footprint "eagle-import:RESC3216X71")
      (libsource (lib "eagle-import") (part "R-EU-3216"))
    )
    (comp (ref "R308")
      (value "2M")
      (footprint "eagle-import:RESC3216X71")
      (libsource (lib "eagle-import") (part "R-EU-3216"))
    )
    (comp (ref "R309")
      (value "2M")
      (footprint "eagle-import:RESC3216X71")
      (libsource (lib "eagle-import") (part "R-EU-3216"))
    )
    (comp (ref "R310")
      (value "2k15")
      (footprint "eagle-import:RESC2012X65")
      (libsource (lib "eagle-import") (part "R-EU-2012"))
    )
    (comp (ref "R311")
      (value "2k15")
      (footprint "eagle-import:RESC2012X65")
      (libsource (lib "eagle-import") (part "R-EU-2012"))
    )
    (comp (ref "R312")
      (value "100R")
      (footprint "eagle-import:RESC1608X70")
      (libsource (lib "eagle-import") (part "R-EU-1608"))
    )
    (comp (ref "R313")
      (value "2k15")
      (footprint "eagle-import:RESC2012X65")
      (libsource (lib "eagle-import") (part "R-EU-2012"))
    )
    (comp (ref "R314")
      (value "10k")
      (footprint "eagle-import:RESC1608X70")
      (libsource (lib "eagle-import") (part "R-EU-1608"))
    )
    (comp (ref "SJ301")
      (value "DUT_GND")
      (footprint "eagle-import:SJW")
      (libsource (lib "eagle-import") (part "SJW"))
    )
    (comp (ref "U301")
      (value "MAX743")
      (footprint "eagle-import:SOIC127P1032X265-16")
      (libsource (lib "eagle-import") (part "MAX743W"))
    )
    (comp (ref "U302")
      (value "LP2985")
      (footprint "eagle-import:SOT95P280X145-5")
      (libsource (lib "eagle-import") (part "LP2985"))
    )
    (comp (ref "U303")
      (value "LM2671M")
      (footprint "eagle-import:SOIC127P599X175-8")
      (libsource (lib "eagle-import") (part "LM2671M"))
    )
    (comp (ref "U304")
      (value "AD620")
      (footprint "eagle-import:SOIC127P599X175-8")
      (libsource (lib "eagle-import") (part "AD620R-8"))
    )
    (comp (ref "U305")
      (value "LTC1865_S8")
      (footprint "eagle-import:SOIC127P599X175-8")
      (libsource (lib "eagle-import") (part "LTC1865_S8"))
    )
  )
  (nets
    (net (code "1") (name "+3V3") (class "Default")
      (node (ref "C313") (pin "1") (pinfunction "1_1") (pintype "passive"))
      (node (ref "R411") (pin "2") (pinfunction "2_2") (pintype "passive"))
      (node (ref "R412") (pin "2") (pinfunction "2_2") (pintype "passive"))
      (node (ref "R415") (pin "2") (pinfunction "2_2") (pintype "passive"))
      (node (ref "R416") (pin "2") (pinfunction "2_2") (pintype "passive"))
      (node (ref "U302") (pin "5") (pinfunction "VOUT_5") (pintype "power_in"))
    )
    (net (code "2") (name "+3V_1") (class "Default")
      (node (ref "C109") (pin "1") (pinfunction "1_1") (pintype "passive"))
      (node (ref "C114") (pin "1") (pinfunction "1_1") (pintype "passive"))
      (node (ref "C115") (pin "1") (pinfunction "1_1") (pintype "passive"))
      (node (ref "C319") (pin "1") (pinfunction "1_1") (pintype "passive"))
      (node (ref "C320") (pin "1") (pinfunction "1_1") (pintype "passive"))
      (node (ref "D101") (pin "2") (pinfunction "C2_2") (pintype "passive"))
      (node (ref "D102") (pin "2") (pinfunction "C2_2") (pintype "passive"))
      (node (ref "D304") (pin "2") (pinfunction "C2_2") (pintype "passive"))
      (node (ref "U103") (pin "5") (pinfunction "VOUT_5") (pintype "power_in"))
      (node (ref "U105") (pin "8") (pinfunction "VCC_8") (pintype "power_in"))
      (node (ref "U305") (pin "8") (pinfunction "VCC_8") (pintype "power_in"))
    )
    (net (code "3") (name "+3V_2") (class "Default")
      (node (ref "C211") (pin "1") (pinfunction "1_1") (pintype "passive"))
      (node (ref "C214") (pin "1") (pinfunction "1_1") (pintype "passive"))
      (node (ref "C215") (pin "1") (pinfunction "1_1") (pintype "passive"))
      (node (ref "D201") (pin "2") (pinfunction "C2_2") (pintype "passive"))
      (node (ref "D202") (pin "2") (pinfunction "C2_2") (pintype "passive"))
      (node (ref "U203") (pin "5") (pinfunction "VOUT_5") (pintype "power_in"))
      (node (ref "U205") (pin "8") (pinfunction "VCC_8") (pintype "power_in"))
    )
    (net (code "4") (name "+5V") (class "Default")
      (node (ref "C101") (pin "1") (pinfunction "1_1") (pintype "passive"))
      (node (ref "C102") (pin "1") (pinfunction "1_1") (pintype "passive"))
      (node (ref "C205") (pin "1") (pinfunction "1_1") (pintype "passive"))
      (node (ref "C206") (pin "1") (pinfunction "1_1") (pintype "passive"))
      (node (ref "C303") (pin "1") (pinfunction "1_1") (pintype "passive"))
      (node (ref "C305") (pin "2") (pinfunction "2_2") (pintype "passive"))
      (node (ref "C312") (pin "1") (pinfunction "1_1") (pintype "passive"))
      (node (ref "C317") (pin "1") (pinfunction "+_1") (pintype "passive"))
      (node (ref "C318") (pin "1") (pinfunction "1_1") (pintype "passive"))
      (node (ref "C401") (pin "1") (pinfunction "1_1") (pintype "passive"))
      (node (ref "C402") (pin "1") (pinfunction "1_1") (pintype "passive"))
      (node (ref "C403") (pin "1") (pinfunction "1_1") (pintype "passive"))
      (node (ref "C404") (pin "1") (pinfunction "1_1") (pintype "passive"))
      (node (ref "C409") (pin "1") (pinfunction "1_1") (pintype "passive"))
      (node (ref "C410") (pin "1") (pinfunction "1_1") (pintype "passive"))
      (node (ref "C413") (pin "1") (pinfunction "1_1") (pintype "passive"))
      (node (ref "C414") (pin "1") (pinfunction "1_1") (pintype "passive"))
      (node (ref "L301") (pin "1") (pinfunction "1_1") (pintype "passive"))
      (node (ref "L303") (pin "2") (pinfunction "2_2") (pintype "passive"))
      (node (ref "R103") (pin "2") (pinfunction "2_2") (pintype "passive"))
      (node (ref "R202") (pin "2") (pinfunction "2_2") (pintype "passive"))
      (node (ref "R304") (pin "1") (pinfunction "1_1") (pintype "passive"))
      (node (ref "R403") (pin "2") (pinfunction "2_2") (pintype "passive"))
      (node (ref "R404") (pin "2") (pinfunction "2_2") (pintype "passive"))
      (node (ref "R407") (pin "2") (pinfunction "2_2") (pintype "passive"))
      (node (ref "R408") (pin "2") (pinfunction "2_2") (pintype "passive"))
      (node (ref "R417") (pin "2") (pinfunction "2_2") (pintype "passive"))
      (node (ref "R418") (pin "2") (pinfunction "2_2") (pintype "passive"))
      (node (ref "U101") (pin "2") (pinfunction "VLL_2") (pintype "bidirectional"))
      (node (ref "U201") (pin "2") (pinfunction "VLL_2") (pintype "bidirectional"))
      (node (ref "U301") (pin "12") (pinfunction "V+_12") (pintype "input"))
      (node (ref "U301") (pin "13") (pinfunction "V+_13") (pintype "input"))
      (node (ref "U301") (pin "3") (pinfunction "AV+_3") (pintype "input"))
      (node (ref "U301") (pin "4") (pinfunction "V+_4") (pintype "input"))
      (node (ref "U301") (pin "5") (pinfunction "V+_5") (pintype "input"))
      (node (ref "U302") (pin "1") (pinfunction "VIN_1") (pintype "power_in"))
      (node (ref "U302") (pin "3") (pinfunction "ON/OFF_3") (pintype "input"))
      (node (ref "U401") (pin "8") (pinfunction "VCC_8") (pintype "power_in"))
      (node (ref "U402") (pin "8") (pinfunction "VCC_8") (pintype "power_in"))
      (node (ref "U403") (pin "8") (pinfunction "VCC_8") (pintype "power_in"))
      (node (ref "U404") (pin "8") (pinfunction "VCC_8") (pintype "power_in"))
    )
    (net (code "5") (name "+5V_I") (class "Default")
      (node (ref "C415") (pin "1") (pinfunction "1_1") (pintype "passive"))
      (node (ref "C416") (pin "1") (pinfunction "1_1") (pintype "passive"))
      (node (ref "JP301") (pin "12") (pinfunction "12_12") (pintype "passive"))
      (node (ref "R401") (pin "2") (pinfunction "2_2") (pintype "passive"))
      (node (ref "R402") (pin "2") (pinfunction "2_2") (pintype "passive"))
      (node (ref "R405") (pin "2") (pinfunction "2_2") (pintype "passive"))
      (node (ref "R406") (pin "2") (pinfunction "2_2") (pintype "passive"))
      (node (ref "R409") (pin "2") (pinfunction "2_2") (pintype "passive"))
      (node (ref "R410") (pin "2") (pinfunction "2_2") (pintype "passive"))
      (node (ref "R413") (pin "2") (pinfunction "2_2") (pintype "passive"))
      (node (ref "R414") (pin "2") (pinfunction "2_2") (pintype "passive"))
      (node (ref "R419") (pin "2") (pinfunction "2_2") (pintype "passive"))
      (node (ref "U405") (pin "8") (pinfunction "VCC_8") (pintype "power_in"))
    )
    (net (code "6") (name "+12V") (class "Default")
      (node (ref "C103") (pin "1") (pinfunction "1_1") (pintype "passive"))
      (node (ref "C104") (pin "1") (pinfunction "1_1") (pintype "passive"))
      (node (ref "C105") (pin "1") (pinfunction "1_1") (pintype "passive"))
      (node (ref "C113") (pin "1") (pinfunction "1_1") (pintype "passive"))
      (node (ref "C201") (pin "1") (pinfunction "1_1") (pintype "passive"))
      (node (ref "C202") (pin "1") (pinfunction "1_1") (pintype "passive"))
      (node (ref "C207") (pin "1") (pinfunction "1_1") (pintype "passive"))
      (node (ref "C213") (pin "1") (pinfunction "1_1") (pintype "passive"))
      (node (ref "C315") (pin "1") (pinfunction "+_1") (pintype "passive"))
      (node (ref "C316") (pin "1") (pinfunction "1_1") (pintype "passive"))
      (node (ref "J301") (pin "3") (pinfunction "3_3") (pintype "passive"))
      (node (ref "Q106") (pin "3") (pinfunction "C_3") (pintype "passive"))
      (node (ref "Q208") (pin "3") (pinfunction "C_3") (pintype "passive"))
      (node (ref "R107") (pin "2") (pinfunction "2_2") (pintype "passive"))
      (node (ref "R108") (pin "2") (pinfunction "2_2") (pintype "passive"))
      (node (ref "R212") (pin "2") (pinfunction "2_2") (pintype "passive"))
      (node (ref "R213") (pin "2") (pinfunction "2_2") (pintype "passive"))
      (node (ref "U101") (pin "23") (pinfunction "VCC_23") (pintype "bidirectional"))
      (node (ref "U201") (pin "23") (pinfunction "VCC_23") (pintype "bidirectional"))
      (node (ref "U303") (pin "8") (pinfunction "VIN_8") (pintype "power_in"))
    )
    (net (code "7") (name "+15V") (class "Default")
      (node (ref "C106") (pin "1") (pinfunction "1_1") (pintype "passive"))
      (node (ref "C107") (pin "1") (pinfunction "1_1") (pintype "passive"))
      (node (ref "C116") (pin "1") (pinfunction "1_1") (pintype "passive"))
      (node (ref "C119") (pin "1") (pinfunction "1_1") (pintype "passive"))
      (node (ref "C203") (pin "1") (pinfunction "1_1") (pintype "passive"))
      (node (ref "C204") (pin "1") (pinfunction "1_1") (pintype "passive"))
      (node (ref "C216") (pin "1") (pinfunction "1_1") (pintype "passive"))
      (node (ref "C219") (pin "1") (pinfunction "1_1") (pintype "passive"))
      (node (ref "C321") (pin "1") (pinfunction "1_1") (pintype "passive"))
      (node (ref "Q101") (pin "3") (pinfunction "C_3") (pintype "passive"))
      (node (ref "Q103") (pin "3") (pinfunction "C_3") (pintype "passive"))
      (node (ref "Q201") (pin "3") (pinfunction "C_3") (pintype "passive"))
      (node (ref "Q203") (pin "3") (pinfunction "C_3") (pintype "passive"))
      (node (ref "Q301") (pin "2") (pinfunction "E_2") (pintype "passive"))
      (node (ref "R101") (pin "2") (pinfunction "2_2") (pintype "passive"))
      (node (ref "R201") (pin "2") (pinfunction "2_2") (pintype "passive"))
      (node (ref "U102") (pin "7") (pinfunction "+V_7") (pintype "power_in"))
      (node (ref "U104") (pin "7") (pinfunction "+V_7") (pintype "power_in"))
      (node (ref "U106") (pin "7") (pinfunction "+V_7") (pintype "power_in"))
      (node (ref "U202") (pin "7") (pinfunction "+V_7") (pintype "power_in"))
      (node (ref "U204") (pin "7") (pinfunction "+V_7") (pintype "power_in"))
      (node (ref "U206") (pin "7") (pinfunction "+V_7") (pintype "power_in"))
      (node (ref "U304") (pin "7") (pinfunction "+V_7") (pintype "power_in"))
    )
    (net (code "8") (name "-15V") (class "Default")
      (node (ref "C110") (pin "2") (pinfunction "2_2") (pintype "passive"))
      (node (ref "C111") (pin "2") (pinfunction "2_2") (pintype "passive"))
      (node (ref "C117") (pin "1") (pinfunction "1_1") (pintype "passive"))
      (node (ref "C120") (pin "1") (pinfunction "1_1") (pintype "passive"))
      (node (ref "C208") (pin "2") (pinfunction "2_2") (pintype "passive"))
      (node (ref "C209") (pin "2") (pinfunction "2_2") (pintype "passive"))
      (node (ref "C217") (pin "1") (pinfunction "1_1") (pintype "passive"))
      (node (ref "C220") (pin "1") (pinfunction "1_1") (pintype "passive"))
      (node (ref "C322") (pin "1") (pinfunction "1_1") (pintype "passive"))
      (node (ref "Q102") (pin "3") (pinfunction "C_3") (pintype "passive"))
      (node (ref "Q104") (pin "3") (pinfunction "C_3") (pintype "passive"))
      (node (ref "Q202") (pin "3") (pinfunction "C_3") (pintype "passive"))
      (node (ref "Q204") (pin "3") (pinfunction "C_3") (pintype "passive"))
      (node (ref "Q302") (pin "2") (pinfunction "E_2") (pintype "passive"))
      (node (ref "R106") (pin "1") (pinfunction "1_1") (pintype "passive"))
      (node (ref "R206") (pin "1") (pinfunction "1_1") (pintype "passive"))
      (node (ref "U102") (pin "4") (pinfunction "-V_4") (pintype "power_in"))
      (node (ref "U104") (pin "4") (pinfunction "-V_4") (pintype "power_in"))
      (node (ref "U106") (pin "4") (pinfunction "-V_4") (pintype "power_in"))
      (node (ref "U202") (pin "4") (pinfunction "-V_4") (pintype "power_in"))
      (node (ref "U204") (pin "4") (pinfunction "-V_4") (pintype "power_in"))
      (node (ref "U206") (pin "4") (pinfunction "-V_4") (pintype "power_in"))
      (node (ref "U304") (pin "4") (pinfunction "-V_4") (pintype "power_in"))
    )
    (net (code "9") (name "BYP") (class "Default")
      (node (ref "C406") (pin "1") (pinfunction "1_1") (pintype "passive"))
      (node (ref "R111") (pin "1") (pinfunction "1_1") (pintype "passive"))
      (node (ref "R216") (pin "1") (pinfunction "1_1") (pintype "passive"))
      (node (ref "R404") (pin "1") (pinfunction "1_1") (pintype "passive"))
      (node (ref "U401") (pin "6") (pinfunction "VO2_6") (pintype "output"))
    )
    (net (code "10") (name "BYP_I") (class "Default")
      (node (ref "JP301") (pin "6") (pinfunction "6_6") (pintype "passive"))
      (node (ref "Q402") (pin "1") (pinfunction "B_1") (pintype "passive"))
    )
    (net (code "11") (name "CLR_DAC") (class "Default")
      (node (ref "C407") (pin "1") (pinfunction "1_1") (pintype "passive"))
      (node (ref "R407") (pin "1") (pinfunction "1_1") (pintype "passive"))
      (node (ref "U101") (pin "6") (pinfunction "CLR_6") (pintype "bidirectional"))
      (node (ref "U201") (pin "6") (pinfunction "CLR_6") (pintype "bidirectional"))
      (node (ref "U402") (pin "7") (pinfunction "VO1_7") (pintype "output"))
    )
    (net (code "12") (name "CLR_DAC_I") (class "Default")
      (node (ref "JP301") (pin "5") (pinfunction "5_5") (pintype "passive"))
      (node (ref "Q403") (pin "1") (pinfunction "B_1") (pintype "passive"))
    )
    (net (code "13") (name "CONV_C1") (class "Default")
      (node (ref "C418") (pin "1") (pinfunction "1_1") (pintype "passive"))
      (node (ref "R416") (pin "1") (pinfunction "1_1") (pintype "passive"))
      (node (ref "U105") (pin "1") (pinfunction "CONV_1") (pintype "input"))
      (node (ref "U404") (pin "6") (pinfunction "VO2_6") (pintype "output"))
    )
    (net (code "14") (name "CONV_C1_I") (class "Default")
      (node (ref "JP301") (pin "8") (pinfunction "8_8") (pintype "passive"))
      (node (ref "Q408") (pin "1") (pinfunction "B_1") (pintype "passive"))
    )
    (net (code "15") (name "CONV_C2") (class "Default")
      (node (ref "C405") (pin "1") (pinfunction "1_1") (pintype "passive"))
      (node (ref "R403") (pin "1") (pinfunction "1_1") (pintype "passive"))
      (node (ref "U205") (pin "1") (pinfunction "CONV_1") (pintype "input"))
      (node (ref "U401") (pin "7") (pinfunction "VO1_7") (pintype "output"))
    )
    (net (code "16") (name "CONV_C2_I") (class "Default")
      (node (ref "JP301") (pin "7") (pinfunction "7_7") (pintype "passive"))
      (node (ref "Q401") (pin "1") (pinfunction "B_1") (pintype "passive"))
    )
    (net (code "17") (name "CONV_V") (class "Default")
      (node (ref "C417") (pin "1") (pinfunction "1_1") (pintype "passive"))
      (node (ref "R415") (pin "1") (pinfunction "1_1") (pintype "passive"))
      (node (ref "U305") (pin "1") (pinfunction "CONV_1") (pintype "input"))
      (node (ref "U404") (pin "7") (pinfunction "VO1_7") (pintype "output"))
    )
    (net (code "18") (name "CONV_V_I") (class "Default")
      (node (ref "JP301") (pin "9") (pinfunction "9_9") (pintype "passive"))
      (node (ref "Q407") (pin "1") (pinfunction "B_1") (pintype "passive"))
    )
    (net (code "19") (name "CSEN_H1") (class "Default")
      (node (ref "Q107") (pin "1") (pinfunction "S_1") (pintype "passive"))
      (node (ref "Q107") (pin "2") (pinfunction "S_2") (pintype "passive"))
      (node (ref "Q107") (pin "3") (pinfunction "S_3") (pintype "passive"))
      (node (ref "Q108") (pin "1") (pinfunction "S_1") (pintype "passive"))
      (node (ref "Q108") (pin "2") (pinfunction "S_2") (pintype "passive"))
      (node (ref "Q108") (pin "3") (pinfunction "S_3") (pintype "passive"))
      (node (ref "R109") (pin "1") (pinfunction "1_1") (pintype "passive"))
      (node (ref "R113") (pin "2") (pinfunction "2_2") (pintype "passive"))
      (node (ref "R116") (pin "I1") (pinfunction "I1_I1") (pintype "passive"))
      (node (ref "R117") (pin "I2") (pinfunction "I2_I2") (pintype "passive"))
      (node (ref "U104") (pin "2") (pinfunction "-_2") (pintype "input"))
    )
    (net (code "20") (name "CSEN_H2") (class "Default")
      (node (ref "Q206") (pin "1") (pinfunction "S_1") (pintype "passive"))
      (node (ref "Q206") (pin "2") (pinfunction "S_2") (pintype "passive"))
      (node (ref "Q206") (pin "3") (pinfunction "S_3") (pintype "passive"))
      (node (ref "Q207") (pin "1") (pinfunction "S_1") (pintype "passive"))
      (node (ref "Q207") (pin "2") (pinfunction "S_2") (pintype "passive"))
      (node (ref "Q207") (pin "3") (pinfunction "S_3") (pintype "passive"))
      (node (ref "R207") (pin "1") (pinfunction "1_1") (pintype "passive"))
      (node (ref "R214") (pin "I1") (pinfunction "I1_I1") (pintype "passive"))
      (node (ref "R215") (pin "I2") (pinfunction "I2_I2") (pintype "passive"))
      (node (ref "R217") (pin "1") (pinfunction "1_1") (pintype "passive"))
      (node (ref "U204") (pin "2") (pinfunction "-_2") (pintype "input"))
    )
    (net (code "21") (name "CSEN_L1") (class "Default")
      (node (ref "Q105") (pin "3") (pinfunction "S_3") (pintype "passive"))
      (node (ref "Q107") (pin "5") (pinfunction "D_5") (pintype "passive"))
      (node (ref "Q107") (pin "6") (pinfunction "D_6") (pintype "passive"))
      (node (ref "Q107") (pin "7") (pinfunction "D_7") (pintype "passive"))
      (node (ref "Q107") (pin "8") (pinfunction "D_8") (pintype "passive"))
      (node (ref "Q108") (pin "5") (pinfunction "D_5") (pintype "passive"))
      (node (ref "Q108") (pin "6") (pinfunction "D_6") (pintype "passive"))
      (node (ref "Q108") (pin "7") (pinfunction "D_7") (pintype "passive"))
      (node (ref "Q108") (pin "8") (pinfunction "D_8") (pintype "passive"))
      (node (ref "R109") (pin "2") (pinfunction "2_2") (pintype "passive"))
      (node (ref "U102") (pin "5") (pinfunction "REF_5") (pintype "passive"))
      (node (ref "U104") (pin "3") (pinfunction "+_3") (pintype "input"))
    )
    (net (code "22") (name "CSEN_L2") (class "Default")
      (node (ref "Q205") (pin "3") (pinfunction "S_3") (pintype "passive"))
      (node (ref "Q206") (pin "5") (pinfunction "D_5") (pintype "passive"))
      (node (ref "Q206") (pin "6") (pinfunction "D_6") (pintype "passive"))
      (node (ref "Q206") (pin "7") (pinfunction "D_7") (pintype "passive"))
      (node (ref "Q206") (pin "8") (pinfunction "D_8") (pintype "passive"))
      (node (ref "Q207") (pin "5") (pinfunction "D_5") (pintype "passive"))
      (node (ref "Q207") (pin "6") (pinfunction "D_6") (pintype "passive"))
      (node (ref "Q207") (pin "7") (pinfunction "D_7") (pintype "passive"))
      (node (ref "Q207") (pin "8") (pinfunction "D_8") (pintype "passive"))
      (node (ref "R207") (pin "2") (pinfunction "2_2") (pintype "passive"))
      (node (ref "U202") (pin "5") (pinfunction "REF_5") (pintype "passive"))
      (node (ref "U204") (pin "3") (pinfunction "+_3") (pintype "input"))
    )
    (net (code "23") (name "DUT+") (class "Default")
      (node (ref "MOV101") (pin "2") (pinfunction "2_2") (pintype "passive"))
      (node (ref "MOV201") (pin "2") (pinfunction "2_2") (pintype "passive"))
      (node (ref "Q105") (pin "2") (pinfunction "D_2") (pintype "passive"))
      (node (ref "Q205") (pin "2") (pinfunction "D_2") (pintype "passive"))
    )
    (net (code "24") (name "DUT-") (class "Default")
      (node (ref "MOV101") (pin "1") (pinfunction "1_1") (pintype "passive"))
      (node (ref "MOV201") (pin "1") (pinfunction "1_1") (pintype "passive"))
      (node (ref "R116") (pin "I2") (pinfunction "I2_I2") (pintype "passive"))
      (node (ref "R117") (pin "I1") (pinfunction "I1_I1") (pintype "passive"))
      (node (ref "R214") (pin "I2") (pinfunction "I2_I2") (pintype "passive"))
      (node (ref "R215") (pin "I1") (pinfunction "I1_I1") (pintype "passive"))
      (node (ref "SJ301") (pin "2") (pinfunction "2_2") (pintype "passive"))
    )
    (net (code "25") (name "GND") (class "Default")
      (node (ref "C101") (pin "2") (pinfunction "2_2") (pintype "passive"))
      (node (ref "C102") (pin "2") (pinfunction "2_2") (pintype "passive"))
      (node (ref "C105") (pin "2") (pinfunction "2_2") (pintype "passive"))
      (node (ref "C106") (pin "2") (pinfunction "2_2") (pintype "passive"))
      (node (ref "C107") (pin "2") (pinfunction "2_2") (pintype "passive"))
      (node (ref "C108") (pin "2") (pinfunction "2_2") (pintype "passive"))
      (node (ref "C109") (pin "2") (pinfunction "2_2") (pintype "passive"))
      (node (ref "C110") (pin "1") (pinfunction "1_1") (pintype "passive"))
      (node (ref "C111") (pin "1") (pinfunction "1_1") (pintype "passive"))
      (node (ref "C112") (pin "2") (pinfunction "2_2") (pintype "passive"))
      (node (ref "C113") (pin "2") (pinfunction "2_2") (pintype "passive"))
      (node (ref "C114") (pin "2") (pinfunction "2_2") (pintype "passive"))
      (node (ref "C115") (pin "2") (pinfunction "2_2") (pintype "passive"))
      (node (ref "C116") (pin "2") (pinfunction "2_2") (pintype "passive"))
      (node (ref "C117") (pin "2") (pinfunction "2_2") (pintype "passive"))
      (node (ref "C118") (pin "2") (pinfunction "2_2") (pintype "passive"))
      (node (ref "C119") (pin "2") (pinfunction "2_2") (pintype "passive"))
      (node (ref "C120") (pin "2") (pinfunction "2_2") (pintype "passive"))
      (node (ref "C121") (pin "2") (pinfunction "2_2") (pintype "passive"))
      (node (ref "C203") (pin "2") (pinfunction "2_2") (pintype "passive"))
      (node (ref "C204") (pin "2") (pinfunction "2_2") (pintype "passive"))
      (node (ref "C205") (pin "2") (pinfunction "2_2") (pintype "passive"))
      (node (ref "C206") (pin "2") (pinfunction "2_2") (pintype "passive"))
      (node (ref "C207") (pin "2") (pinfunction "2_2") (pintype "passive"))
      (node (ref "C208") (pin "1") (pinfunction "1_1") (pintype "passive"))
      (node (ref "C209") (pin "1") (pinfunction "1_1") (pintype "passive"))
      (node (ref "C210") (pin "2") (pinfunction "2_2") (pintype "passive"))
      (node (ref "C211") (pin "2") (pinfunction "2_2") (pintype "passive"))
      (node (ref "C212") (pin "2") (pinfunction "2_2") (pintype "passive"))
      (node (ref "C213") (pin "2") (pinfunction "2_2") (pintype "passive"))
      (node (ref "C214") (pin "2") (pinfunction "2_2") (pintype "passive"))
      (node (ref "C215") (pin "2") (pinfunction "2_2") (pintype "passive"))
      (node (ref "C216") (pin "2") (pinfunction "2_2") (pintype "passive"))
      (node (ref "C217") (pin "2") (pinfunction "2_2") (pintype "passive"))
      (node (ref "C218") (pin "2") (pinfunction "2_2") (pintype "passive"))
      (node (ref "C219") (pin "2") (pinfunction "2_2") (pintype "passive"))
      (node (ref "C220") (pin "2") (pinfunction "2_2") (pintype "passive"))
      (node (ref "C221") (pin "2") (pinfunction "2_2") (pintype "passive"))
      (node (ref "C301") (pin "2") (pinfunction "-_2") (pintype "passive"))
      (node (ref "C302") (pin "2") (pinfunction "2_2") (pintype "passive"))
      (node (ref "C303") (pin "2") (pinfunction "2_2") (pintype "passive"))
      (node (ref "C304") (pin "1") (pinfunction "1_1") (pintype "passive"))
      (node (ref "C305") (pin "1") (pinfunction "1_1") (pintype "passive"))
      (node (ref "C306") (pin "2") (pinfunction "2_2") (pintype "passive"))
      (node (ref "C307") (pin "1") (pinfunction "+_1") (pintype "passive"))
      (node (ref "C308") (pin "2") (pinfunction "2_2") (pintype "passive"))
      (node (ref "C309") (pin "2") (pinfunction "2_2") (pintype "passive"))
      (node (ref "C310") (pin "2") (pinfunction "2_2") (pintype "passive"))
      (node (ref "C312") (pin "2") (pinfunction "2_2") (pintype "passive"))
      (node (ref "C313") (pin "2") (pinfunction "2_2") (pintype "passive"))
      (node (ref "C314") (pin "2") (pinfunction "2_2") (pintype "passive"))
      (node (ref "C315") (pin "2") (pinfunction "-_2") (pintype "passive"))
      (node (ref "C316") (pin "2") (pinfunction "2_2") (pintype "passive"))
      (node (ref "C317") (pin "2") (pinfunction "-_2") (pintype "passive"))
      (node (ref "C318") (pin "2") (pinfunction "2_2") (pintype "passive"))
      (node (ref "C319") (pin "2") (pinfunction "2_2") (pintype "passive"))
      (node (ref "C320") (pin "2") (pinfunction "2_2") (pintype "passive"))
      (node (ref "C321") (pin "2") (pinfunction "2_2") (pintype "passive"))
      (node (ref "C322") (pin "2") (pinfunction "2_2") (pintype "passive"))
      (node (ref "C323") (pin "2") (pinfunction "2_2") (pintype "passive"))
      (node (ref "C401") (pin "2") (pinfunction "2_2") (pintype "passive"))
      (node (ref "C402") (pin "2") (pinfunction "2_2") (pintype "passive"))
      (node (ref "C403") (pin "2") (pinfunction "2_2") (pintype "passive"))
      (node (ref "C404") (pin "2") (pinfunction "2_2") (pintype "passive"))
      (node (ref "C405") (pin "2") (pinfunction "2_2") (pintype "passive"))
      (node (ref "C406") (pin "2") (pinfunction "2_2") (pintype "passive"))
      (node (ref "C407") (pin "2") (pinfunction "2_2") (pintype "passive"))
      (node (ref "C408") (pin "2") (pinfunction "2_2") (pintype "passive"))
      (node (ref "C409") (pin "2") (pinfunction "2_2") (pintype "passive"))
      (node (ref "C410") (pin "2") (pinfunction "2_2") (pintype "passive"))
      (node (ref "C411") (pin "2") (pinfunction "2_2") (pintype "passive"))
      (node (ref "C412") (pin "2") (pinfunction "2_2") (pintype "passive"))
      (node (ref "C413") (pin "2") (pinfunction "2_2") (pintype "passive"))
      (node (ref "C414") (pin "2") (pinfunction "2_2") (pintype "passive"))
      (node (ref "C417") (pin "2") (pinfunction "2_2") (pintype "passive"))
      (node (ref "C418") (pin "2") (pinfunction "2_2") (pintype "passive"))
      (node (ref "D101") (pin "1") (pinfunction "A1_1") (pintype "passive"))
      (node (ref "D102") (pin "1") (pinfunction "A1_1") (pintype "passive"))
      (node (ref "D201") (pin "1") (pinfunction "A1_1") (pintype "passive"))
      (node (ref "D202") (pin "1") (pinfunction "A1_1") (pintype "passive"))
      (node (ref "D303") (pin "2") (pinfunction "A_2") (pintype "passive"))
      (node (ref "D304") (pin "1") (pinfunction "A1_1") (pintype "passive"))
      (node (ref "J301") (pin "1") (pinfunction "1_1") (pintype "passive"))
      (node (ref "L302") (pin "2") (pinfunction "2_2") (pintype "passive"))
      (node (ref "Q109") (pin "2") (pinfunction "E_2") (pintype "passive"))
      (node (ref "Q110") (pin "3") (pinfunction "C_3") (pintype "passive"))
      (node (ref "Q209") (pin "2") (pinfunction "E_2") (pintype "passive"))
      (node (ref "Q210") (pin "3") (pinfunction "C_3") (pintype "passive"))
      (node (ref "Q409") (pin "3") (pinfunction "C_3") (pintype "passive"))
      (node (ref "R303") (pin "2") (pinfunction "2_2") (pintype "passive"))
      (node (ref "R314") (pin "1") (pinfunction "1_1") (pintype "passive"))
      (node (ref "SJ301") (pin "1") (pinfunction "1_1") (pintype "passive"))
      (node (ref "U101") (pin "11") (pinfunction "GND_11") (pintype "bidirectional"))
      (node (ref "U101") (pin "4") (pinfunction "RS2_4") (pintype "bidirectional"))
      (node (ref "U101") (pin "5") (pinfunction "RS1_5") (pintype "bidirectional"))
      (node (ref "U102") (pin "2") (pinfunction "-_2") (pintype "input"))
      (node (ref "U103") (pin "2") (pinfunction "GND_2") (pintype "power_in"))
      (node (ref "U104") (pin "5") (pinfunction "REF_5") (pintype "passive"))
      (node (ref "U105") (pin "4") (pinfunction "GND_4") (pintype "bidirectional"))
      (node (ref "U106") (pin "5") (pinfunction "REF_5") (pintype "passive"))
      (node (ref "U201") (pin "11") (pinfunction "GND_11") (pintype "bidirectional"))
      (node (ref "U201") (pin "4") (pinfunction "RS2_4") (pintype "bidirectional"))
      (node (ref "U201") (pin "5") (pinfunction "RS1_5") (pintype "bidirectional"))
      (node (ref "U202") (pin "2") (pinfunction "-_2") (pintype "input"))
      (node (ref "U203") (pin "2") (pinfunction "GND_2") (pintype "power_in"))
      (node (ref "U204") (pin "5") (pinfunction "REF_5") (pintype "passive"))
      (node (ref "U205") (pin "4") (pinfunction "GND_4") (pintype "bidirectional"))
      (node (ref "U206") (pin "5") (pinfunction "REF_5") (pintype "passive"))
      (node (ref "U301") (pin "11") (pinfunction "12/15_11") (pintype "input"))
      (node (ref "U301") (pin "14") (pinfunction "GND_14") (pintype "power_in"))
      (node (ref "U301") (pin "2") (pinfunction "AGND_2") (pintype "power_in"))
      (node (ref "U302") (pin "2") (pinfunction "GND_2") (pintype "power_in"))
      (node (ref "U303") (pin "7") (pinfunction "GND_7") (pintype "power_in"))
      (node (ref "U304") (pin "5") (pinfunction "REF_5") (pintype "passive"))
      (node (ref "U305") (pin "4") (pinfunction "GND_4") (pintype "bidirectional"))
      (node (ref "U401") (pin "5") (pinfunction "GND_5") (pintype "power_in"))
      (node (ref "U402") (pin "5") (pinfunction "GND_5") (pintype "power_in"))
      (node (ref "U403") (pin "5") (pinfunction "GND_5") (pintype "power_in"))
      (node (ref "U404") (pin "5") (pinfunction "GND_5") (pintype "power_in"))
      (node (ref "U405") (pin "1") (pinfunction "A1_1") (pintype "input"))
      (node (ref "U405") (pin "2") (pinfunction "C1_2") (pintype "input"))
      (node (ref "U405") (pin "3") (pinfunction "C2_3") (pintype "input"))
    )
    (net (code "26") (name "GNDI") (class "Default")
      (node (ref "C415") (pin "2") (pinfunction "2_2") (pintype "passive"))
      (node (ref "C416") (pin "2") (pinfunction "2_2") (pintype "passive"))
      (node (ref "C419") (pin "2") (pinfunction "2_2") (pintype "passive"))
      (node (ref "JP301") (pin "10") (pinfunction "10_10") (pintype "passive"))
      (node (ref "JP301") (pin "11") (pinfunction "11_11") (pintype "passive"))
      (node (ref "Q401") (pin "3") (pinfunction "C_3") (pintype "passive"))
      (node (ref "Q402") (pin "3") (pinfunction "C_3") (pintype "passive"))
      (node (ref "Q403") (pin "3") (pinfunction "C_3") (pintype "passive"))
      (node (ref "Q404") (pin "3") (pinfunction "C_3") (pintype "passive"))
      (node (ref "Q405") (pin "3") (pinfunction "C_3") (pintype "passive"))
      (node (ref "Q406") (pin "3") (pinfunction "C_3") (pintype "passive"))
      (node (ref "Q407") (pin "3") (pinfunction "C_3") (pintype "passive"))
      (node (ref "Q408") (pin "3") (pinfunction "C_3") (pintype "passive"))
      (node (ref "U401") (pin "2") (pinfunction "C1_2") (pintype "input"))
      (node (ref "U401") (pin "3") (pinfunction "C2_3") (pintype "input"))
      (node (ref "U402") (pin "2") (pinfunction "C1_2") (pintype "input"))
      (node (ref "U402") (pin "3") (pinfunction "C2_3") (pintype "input"))
      (node (ref "U403") (pin "2") (pinfunction "C1_2") (pintype "input"))
      (node (ref "U403") (pin "3") (pinfunction "C2_3") (pintype "input"))
      (node (ref "U404") (pin "2") (pinfunction "C1_2") (pintype "input"))
      (node (ref "U404") (pin "3") (pinfunction "C2_3") (pintype "input"))
      (node (ref "U405") (pin "5") (pinfunction "GND_5") (pintype "power_in"))
      (node (ref "U405") (pin "7") (pinfunction "VO1_7") (pintype "output"))
    )
    (net (code "27") (name "LATCH_DAC") (class "Default")
      (node (ref "C408") (pin "1") (pinfunction "1_1") (pintype "passive"))
      (node (ref "R408") (pin "1") (pinfunction "1_1") (pintype "passive"))
      (node (ref "U101") (pin "7") (pinfunction "LATCH_7") (pintype "bidirectional"))
      (node (ref "U201") (pin "7") (pinfunction "LATCH_7") (pintype "bidirectional"))
      (node (ref "U402") (pin "6") (pinfunction "VO2_6") (pintype "output"))
    )
    (net (code "28") (name "LATCH_DAC_I") (class "Default")
      (node (ref "JP301") (pin "4") (pinfunction "4_4") (pintype "passive"))
      (node (ref "Q404") (pin "1") (pinfunction "B_1") (pintype "passive"))
    )
    (net (code "29") (name "LGATE_1") (class "Default")
      (node (ref "Q105") (pin "1") (pinfunction "G_1") (pintype "passive"))
      (node (ref "R102") (pin "1") (pinfunction "1_1") (pintype "passive"))
      (node (ref "R105") (pin "2") (pinfunction "2_2") (pintype "passive"))
    )
    (net (code "30") (name "LGATE_2") (class "Default")
      (node (ref "Q205") (pin "1") (pinfunction "G_1") (pintype "passive"))
      (node (ref "R203") (pin "1") (pinfunction "1_1") (pintype "passive"))
      (node (ref "R205") (pin "2") (pinfunction "2_2") (pintype "passive"))
    )
    (net (code "31") (name "MISO") (class "Default")
      (node (ref "Q409") (pin "1") (pinfunction "B_1") (pintype "passive"))
      (node (ref "R417") (pin "1") (pinfunction "1_1") (pintype "passive"))
      (node (ref "U105") (pin "6") (pinfunction "SDO_6") (pintype "output"))
      (node (ref "U205") (pin "6") (pinfunction "SDO_6") (pintype "output"))
      (node (ref "U305") (pin "6") (pinfunction "SDO_6") (pintype "output"))
    )
    (net (code "32") (name "MISO_I") (class "Default")
      (node (ref "C419") (pin "1") (pinfunction "1_1") (pintype "passive"))
      (node (ref "JP301") (pin "1") (pinfunction "1_1") (pintype "passive"))
      (node (ref "R419") (pin "1") (pinfunction "1_1") (pintype "passive"))
      (node (ref "U405") (pin "6") (pinfunction "VO2_6") (pintype "output"))
    )
    (net (code "33") (name "MOSI") (class "Default")
      (node (ref "C412") (pin "1") (pinfunction "1_1") (pintype "passive"))
      (node (ref "R412") (pin "1") (pinfunction "1_1") (pintype "passive"))
      (node (ref "U105") (pin "5") (pinfunction "SDI_5") (pintype "input"))
      (node (ref "U201") (pin "9") (pinfunction "SDI_9") (pintype "bidirectional"))
      (node (ref "U205") (pin "5") (pinfunction "SDI_5") (pintype "input"))
      (node (ref "U305") (pin "5") (pinfunction "SDI_5") (pintype "input"))
      (node (ref "U403") (pin "6") (pinfunction "VO2_6") (pintype "output"))
    )
    (net (code "34") (name "MOSI_I") (class "Default")
      (node (ref "JP301") (pin "2") (pinfunction "2_2") (pintype "passive"))
      (node (ref "Q406") (pin "1") (pinfunction "B_1") (pintype "passive"))
    )
    (net (code "35") (name "N$34") (class "Default")
      (node (ref "R114") (pin "1") (pinfunction "1_1") (pintype "passive"))
      (node (ref "R115") (pin "1") (pinfunction "1_1") (pintype "passive"))
      (node (ref "U106") (pin "3") (pinfunction "+_3") (pintype "input"))
    )
    (net (code "36") (name "N$37") (class "Default")
      (node (ref "R118") (pin "2") (pinfunction "2_2") (pintype "passive"))
      (node (ref "R119") (pin "2") (pinfunction "2_2") (pintype "passive"))
      (node (ref "U106") (pin "2") (pinfunction "-_2") (pintype "input"))
    )
    (net (code "37") (name "N$54") (class "Default")
      (node (ref "R210") (pin "2") (pinfunction "2_2") (pintype "passive"))
      (node (ref "R211") (pin "2") (pinfunction "2_2") (pintype "passive"))
      (node (ref "U206") (pin "3") (pinfunction "+_3") (pintype "input"))
    )
    (net (code "38") (name "N$63") (class "Default")
      (node (ref "R218") (pin "1") (pinfunction "1_1") (pintype "passive"))
      (node (ref "R219") (pin "1") (pinfunction "1_1") (pintype "passive"))
      (node (ref "U206") (pin "2") (pinfunction "-_2") (pintype "input"))
    )
    (net (code "39") (name "Net-(C301-+)") (class "Default")
      (node (ref "C301") (pin "1") (pinfunction "+_1") (pintype "passive"))
      (node (ref "D301") (pin "1") (pinfunction "C_1") (pintype "passive"))
      (node (ref "Q301") (pin "3") (pinfunction "C_3") (pintype "passive"))
      (node (ref "R301") (pin "1") (pinfunction "1_1") (pintype "passive"))
      (node (ref "U301") (pin "16") (pinfunction "FB+_16") (pintype "input"))
    )
    (net (code "40") (name "Net-(C307--)") (class "Default")
      (node (ref "C307") (pin "2") (pinfunction "-_2") (pintype "passive"))
      (node (ref "D302") (pin "2") (pinfunction "A_2") (pintype "passive"))
      (node (ref "Q302") (pin "3") (pinfunction "C_3") (pintype "passive"))
      (node (ref "R302") (pin "1") (pinfunction "1_1") (pintype "passive"))
      (node (ref "U301") (pin "9") (pinfunction "FB-_9") (pintype "input"))
    )
    (net (code "41") (name "Net-(D101-C1A2)") (class "Default")
      (node (ref "D101") (pin "3") (pinfunction "C1A2_3") (pintype "passive"))
      (node (ref "R121") (pin "1") (pinfunction "1_1") (pintype "passive"))
      (node (ref "U104") (pin "6") (pinfunction "OUT_6") (pintype "output"))
    )
    (net (code "42") (name "Net-(D102-C1A2)") (class "Default")
      (node (ref "D102") (pin "3") (pinfunction "C1A2_3") (pintype "passive"))
      (node (ref "R123") (pin "1") (pinfunction "1_1") (pintype "passive"))
      (node (ref "U106") (pin "6") (pinfunction "OUT_6") (pintype "output"))
    )
    (net (code "43") (name "Net-(D201-C1A2)") (class "Default")
      (node (ref "D201") (pin "3") (pinfunction "C1A2_3") (pintype "passive"))
      (node (ref "R221") (pin "1") (pinfunction "1_1") (pintype "passive"))
      (node (ref "U204") (pin "6") (pinfunction "OUT_6") (pintype "output"))
    )
    (net (code "44") (name "Net-(D202-C1A2)") (class "Default")
      (node (ref "D202") (pin "3") (pinfunction "C1A2_3") (pintype "passive"))
      (node (ref "R223") (pin "1") (pinfunction "1_1") (pintype "passive"))
      (node (ref "U206") (pin "6") (pinfunction "OUT_6") (pintype "output"))
    )
    (net (code "45") (name "Net-(D301-A)") (class "Default")
      (node (ref "D301") (pin "2") (pinfunction "A_2") (pintype "passive"))
      (node (ref "L301") (pin "2") (pinfunction "2_2") (pintype "passive"))
      (node (ref "U301") (pin "15") (pinfunction "LX+_15") (pintype "passive"))
    )
    (net (code "46") (name "Net-(D302-C)") (class "Default")
      (node (ref "D302") (pin "1") (pinfunction "C_1") (pintype "passive"))
      (node (ref "L302") (pin "1") (pinfunction "1_1") (pintype "passive"))
      (node (ref "U301") (pin "10") (pinfunction "LX-_10") (pintype "passive"))
    )
    (net (code "47") (name "Net-(D303-C)") (class "Default")
      (node (ref "C311") (pin "2") (pinfunction "2_2") (pintype "passive"))
      (node (ref "D303") (pin "1") (pinfunction "C_1") (pintype "passive"))
      (node (ref "L303") (pin "1") (pinfunction "1_1") (pintype "passive"))
      (node (ref "U303") (pin "6") (pinfunction "VSW_6") (pintype "output"))
    )
    (net (code "48") (name "Net-(D304-C1A2)") (class "Default")
      (node (ref "D304") (pin "3") (pinfunction "C1A2_3") (pintype "passive"))
      (node (ref "R312") (pin "1") (pinfunction "1_1") (pintype "passive"))
      (node (ref "U304") (pin "6") (pinfunction "OUT_6") (pintype "output"))
    )
    (net (code "49") (name "Net-(Q101-B)") (class "Default")
      (node (ref "Q101") (pin "1") (pinfunction "B_1") (pintype "passive"))
      (node (ref "Q102") (pin "2") (pinfunction "E_2") (pintype "passive"))
      (node (ref "R101") (pin "1") (pinfunction "1_1") (pintype "passive"))
    )
    (net (code "50") (name "Net-(Q101-E)") (class "Default")
      (node (ref "Q101") (pin "2") (pinfunction "E_2") (pintype "passive"))
      (node (ref "R102") (pin "2") (pinfunction "2_2") (pintype "passive"))
    )
    (net (code "51") (name "Net-(Q102-B)") (class "Default")
      (node (ref "Q102") (pin "1") (pinfunction "B_1") (pintype "passive"))
      (node (ref "Q103") (pin "1") (pinfunction "B_1") (pintype "passive"))
      (node (ref "U102") (pin "6") (pinfunction "OUT_6") (pintype "output"))
    )
    (net (code "52") (name "Net-(Q103-E)") (class "Default")
      (node (ref "Q103") (pin "2") (pinfunction "E_2") (pintype "passive"))
      (node (ref "Q104") (pin "1") (pinfunction "B_1") (pintype "passive"))
      (node (ref "R106") (pin "2") (pinfunction "2_2") (pintype "passive"))
    )
    (net (code "53") (name "Net-(Q104-E)") (class "Default")
      (node (ref "Q104") (pin "2") (pinfunction "E_2") (pintype "passive"))
      (node (ref "R105") (pin "1") (pinfunction "1_1") (pintype "passive"))
    )
    (net (code "54") (name "Net-(Q106-B)") (class "Default")
      (node (ref "Q106") (pin "1") (pinfunction "B_1") (pintype "passive"))
      (node (ref "Q109") (pin "3") (pinfunction "C_3") (pintype "passive"))
      (node (ref "Q110") (pin "1") (pinfunction "B_1") (pintype "passive"))
      (node (ref "R108") (pin "1") (pinfunction "1_1") (pintype "passive"))
    )
    (net (code "55") (name "Net-(Q106-E)") (class "Default")
      (node (ref "Q106") (pin "2") (pinfunction "E_2") (pintype "passive"))
      (node (ref "Q110") (pin "2") (pinfunction "E_2") (pintype "passive"))
      (node (ref "R110") (pin "1") (pinfunction "1_1") (pintype "passive"))
      (node (ref "R112") (pin "1") (pinfunction "1_1") (pintype "passive"))
      (node (ref "R113") (pin "1") (pinfunction "1_1") (pintype "passive"))
    )
    (net (code "56") (name "Net-(Q107-G)") (class "Default")
      (node (ref "Q107") (pin "4") (pinfunction "G_4") (pintype "passive"))
      (node (ref "R110") (pin "2") (pinfunction "2_2") (pintype "passive"))
    )
    (net (code "57") (name "Net-(Q108-G)") (class "Default")
      (node (ref "Q108") (pin "4") (pinfunction "G_4") (pintype "passive"))
      (node (ref "R112") (pin "2") (pinfunction "2_2") (pintype "passive"))
    )
    (net (code "58") (name "Net-(Q109-B)") (class "Default")
      (node (ref "Q109") (pin "1") (pinfunction "B_1") (pintype "passive"))
      (node (ref "R107") (pin "1") (pinfunction "1_1") (pintype "passive"))
      (node (ref "R111") (pin "2") (pinfunction "2_2") (pintype "passive"))
    )
    (net (code "59") (name "Net-(Q201-B)") (class "Default")
      (node (ref "Q201") (pin "1") (pinfunction "B_1") (pintype "passive"))
      (node (ref "Q202") (pin "2") (pinfunction "E_2") (pintype "passive"))
      (node (ref "R201") (pin "1") (pinfunction "1_1") (pintype "passive"))
    )
    (net (code "60") (name "Net-(Q201-E)") (class "Default")
      (node (ref "Q201") (pin "2") (pinfunction "E_2") (pintype "passive"))
      (node (ref "R203") (pin "2") (pinfunction "2_2") (pintype "passive"))
    )
    (net (code "61") (name "Net-(Q202-B)") (class "Default")
      (node (ref "Q202") (pin "1") (pinfunction "B_1") (pintype "passive"))
      (node (ref "Q203") (pin "1") (pinfunction "B_1") (pintype "passive"))
      (node (ref "U202") (pin "6") (pinfunction "OUT_6") (pintype "output"))
    )
    (net (code "62") (name "Net-(Q203-E)") (class "Default")
      (node (ref "Q203") (pin "2") (pinfunction "E_2") (pintype "passive"))
      (node (ref "Q204") (pin "1") (pinfunction "B_1") (pintype "passive"))
      (node (ref "R206") (pin "2") (pinfunction "2_2") (pintype "passive"))
    )
    (net (code "63") (name "Net-(Q204-E)") (class "Default")
      (node (ref "Q204") (pin "2") (pinfunction "E_2") (pintype "passive"))
      (node (ref "R205") (pin "1") (pinfunction "1_1") (pintype "passive"))
    )
    (net (code "64") (name "Net-(Q206-G)") (class "Default")
      (node (ref "Q206") (pin "4") (pinfunction "G_4") (pintype "passive"))
      (node (ref "R208") (pin "2") (pinfunction "2_2") (pintype "passive"))
    )
    (net (code "65") (name "Net-(Q207-G)") (class "Default")
      (node (ref "Q207") (pin "4") (pinfunction "G_4") (pintype "passive"))
      (node (ref "R209") (pin "2") (pinfunction "2_2") (pintype "passive"))
    )
    (net (code "66") (name "Net-(Q208-B)") (class "Default")
      (node (ref "Q208") (pin "1") (pinfunction "B_1") (pintype "passive"))
      (node (ref "Q209") (pin "3") (pinfunction "C_3") (pintype "passive"))
      (node (ref "Q210") (pin "1") (pinfunction "B_1") (pintype "passive"))
      (node (ref "R213") (pin "1") (pinfunction "1_1") (pintype "passive"))
    )
    (net (code "67") (name "Net-(Q208-E)") (class "Default")
      (node (ref "Q208") (pin "2") (pinfunction "E_2") (pintype "passive"))
      (node (ref "Q210") (pin "2") (pinfunction "E_2") (pintype "passive"))
      (node (ref "R208") (pin "1") (pinfunction "1_1") (pintype "passive"))
      (node (ref "R209") (pin "1") (pinfunction "1_1") (pintype "passive"))
      (node (ref "R217") (pin "2") (pinfunction "2_2") (pintype "passive"))
    )
    (net (code "68") (name "Net-(Q209-B)") (class "Default")
      (node (ref "Q209") (pin "1") (pinfunction "B_1") (pintype "passive"))
      (node (ref "R212") (pin "1") (pinfunction "1_1") (pintype "passive"))
      (node (ref "R216") (pin "2") (pinfunction "2_2") (pintype "passive"))
    )
    (net (code "69") (name "Net-(Q301-B)") (class "Default")
      (node (ref "C302") (pin "1") (pinfunction "1_1") (pintype "passive"))
      (node (ref "Q301") (pin "1") (pinfunction "B_1") (pintype "passive"))
      (node (ref "R301") (pin "2") (pinfunction "2_2") (pintype "passive"))
    )
    (net (code "70") (name "Net-(Q302-B)") (class "Default")
      (node (ref "C306") (pin "1") (pinfunction "1_1") (pintype "passive"))
      (node (ref "Q302") (pin "1") (pinfunction "B_1") (pintype "passive"))
      (node (ref "R302") (pin "2") (pinfunction "2_2") (pintype "passive"))
    )
    (net (code "71") (name "Net-(Q401-E)") (class "Default")
      (node (ref "Q401") (pin "2") (pinfunction "E_2") (pintype "passive"))
      (node (ref "R401") (pin "1") (pinfunction "1_1") (pintype "passive"))
      (node (ref "U401") (pin "1") (pinfunction "A1_1") (pintype "input"))
    )
    (net (code "72") (name "Net-(Q402-E)") (class "Default")
      (node (ref "Q402") (pin "2") (pinfunction "E_2") (pintype "passive"))
      (node (ref "R402") (pin "1") (pinfunction "1_1") (pintype "passive"))
      (node (ref "U401") (pin "4") (pinfunction "A2_4") (pintype "input"))
    )
    (net (code "73") (name "Net-(Q403-E)") (class "Default")
      (node (ref "Q403") (pin "2") (pinfunction "E_2") (pintype "passive"))
      (node (ref "R405") (pin "1") (pinfunction "1_1") (pintype "passive"))
      (node (ref "U402") (pin "1") (pinfunction "A1_1") (pintype "input"))
    )
    (net (code "74") (name "Net-(Q404-E)") (class "Default")
      (node (ref "Q404") (pin "2") (pinfunction "E_2") (pintype "passive"))
      (node (ref "R406") (pin "1") (pinfunction "1_1") (pintype "passive"))
      (node (ref "U402") (pin "4") (pinfunction "A2_4") (pintype "input"))
    )
    (net (code "75") (name "Net-(Q405-E)") (class "Default")
      (node (ref "Q405") (pin "2") (pinfunction "E_2") (pintype "passive"))
      (node (ref "R409") (pin "1") (pinfunction "1_1") (pintype "passive"))
      (node (ref "U403") (pin "1") (pinfunction "A1_1") (pintype "input"))
    )
    (net (code "76") (name "Net-(Q406-E)") (class "Default")
      (node (ref "Q406") (pin "2") (pinfunction "E_2") (pintype "passive"))
      (node (ref "R410") (pin "1") (pinfunction "1_1") (pintype "passive"))
      (node (ref "U403") (pin "4") (pinfunction "A2_4") (pintype "input"))
    )
    (net (code "77") (name "Net-(Q407-E)") (class "Default")
      (node (ref "Q407") (pin "2") (pinfunction "E_2") (pintype "passive"))
      (node (ref "R413") (pin "1") (pinfunction "1_1") (pintype "passive"))
      (node (ref "U404") (pin "1") (pinfunction "A1_1") (pintype "input"))
    )
    (net (code "78") (name "Net-(Q408-E)") (class "Default")
      (node (ref "Q408") (pin "2") (pinfunction "E_2") (pintype "passive"))
      (node (ref "R414") (pin "1") (pinfunction "1_1") (pintype "passive"))
      (node (ref "U404") (pin "4") (pinfunction "A2_4") (pintype "input"))
    )
    (net (code "79") (name "Net-(Q409-E)") (class "Default")
      (node (ref "Q409") (pin "2") (pinfunction "E_2") (pintype "passive"))
      (node (ref "R418") (pin "1") (pinfunction "1_1") (pintype "passive"))
      (node (ref "U405") (pin "4") (pinfunction "A2_4") (pintype "input"))
    )
    (net (code "80") (name "Net-(R104-Pad1)") (class "Default")
      (node (ref "R104") (pin "1") (pinfunction "1_1") (pintype "passive"))
      (node (ref "U102") (pin "8") (pinfunction "RG_8") (pintype "passive"))
    )
    (net (code "81") (name "Net-(R104-Pad2)") (class "Default")
      (node (ref "R104") (pin "2") (pinfunction "2_2") (pintype "passive"))
      (node (ref "U102") (pin "1") (pinfunction "RG_1") (pintype "passive"))
    )
    (net (code "82") (name "Net-(R114-Pad2)") (class "Default")
      (node (ref "R114") (pin "2") (pinfunction "2_2") (pintype "passive"))
      (node (ref "R116") (pin "E1") (pinfunction "E1_E1") (pintype "passive"))
    )
    (net (code "83") (name "Net-(R115-Pad2)") (class "Default")
      (node (ref "R115") (pin "2") (pinfunction "2_2") (pintype "passive"))
      (node (ref "R117") (pin "E2") (pinfunction "E2_E2") (pintype "passive"))
    )
    (net (code "84") (name "Net-(R116-PadE2)") (class "Default")
      (node (ref "R116") (pin "E2") (pinfunction "E2_E2") (pintype "passive"))
      (node (ref "R118") (pin "1") (pinfunction "1_1") (pintype "passive"))
    )
    (net (code "85") (name "Net-(R117-PadE1)") (class "Default")
      (node (ref "R117") (pin "E1") (pinfunction "E1_E1") (pintype "passive"))
      (node (ref "R119") (pin "1") (pinfunction "1_1") (pintype "passive"))
    )
    (net (code "86") (name "Net-(R120-Pad1)") (class "Default")
      (node (ref "R120") (pin "1") (pinfunction "1_1") (pintype "passive"))
      (node (ref "U104") (pin "8") (pinfunction "RG_8") (pintype "passive"))
    )
    (net (code "87") (name "Net-(R120-Pad2)") (class "Default")
      (node (ref "R120") (pin "2") (pinfunction "2_2") (pintype "passive"))
      (node (ref "U104") (pin "1") (pinfunction "RG_1") (pintype "passive"))
    )
    (net (code "88") (name "Net-(R122-Pad1)") (class "Default")
      (node (ref "R122") (pin "1") (pinfunction "1_1") (pintype "passive"))
      (node (ref "U106") (pin "8") (pinfunction "RG_8") (pintype "passive"))
    )
    (net (code "89") (name "Net-(R122-Pad2)") (class "Default")
      (node (ref "R122") (pin "2") (pinfunction "2_2") (pintype "passive"))
      (node (ref "U106") (pin "1") (pinfunction "RG_1") (pintype "passive"))
    )
    (net (code "90") (name "Net-(R204-Pad1)") (class "Default")
      (node (ref "R204") (pin "1") (pinfunction "1_1") (pintype "passive"))
      (node (ref "U202") (pin "8") (pinfunction "RG_8") (pintype "passive"))
    )
    (net (code "91") (name "Net-(R204-Pad2)") (class "Default")
      (node (ref "R204") (pin "2") (pinfunction "2_2") (pintype "passive"))
      (node (ref "U202") (pin "1") (pinfunction "RG_1") (pintype "passive"))
    )
    (net (code "92") (name "Net-(R210-Pad1)") (class "Default")
      (node (ref "R210") (pin "1") (pinfunction "1_1") (pintype "passive"))
      (node (ref "R214") (pin "E1") (pinfunction "E1_E1") (pintype "passive"))
    )
    (net (code "93") (name "Net-(R211-Pad1)") (class "Default")
      (node (ref "R211") (pin "1") (pinfunction "1_1") (pintype "passive"))
      (node (ref "R215") (pin "E2") (pinfunction "E2_E2") (pintype "passive"))
    )
    (net (code "94") (name "Net-(R214-PadE2)") (class "Default")
      (node (ref "R214") (pin "E2") (pinfunction "E2_E2") (pintype "passive"))
      (node (ref "R219") (pin "2") (pinfunction "2_2") (pintype "passive"))
    )
    (net (code "95") (name "Net-(R215-PadE1)") (class "Default")
      (node (ref "R215") (pin "E1") (pinfunction "E1_E1") (pintype "passive"))
      (node (ref "R218") (pin "2") (pinfunction "2_2") (pintype "passive"))
    )
    (net (code "96") (name "Net-(R220-Pad1)") (class "Default")
      (node (ref "R220") (pin "1") (pinfunction "1_1") (pintype "passive"))
      (node (ref "U204") (pin "8") (pinfunction "RG_8") (pintype "passive"))
    )
    (net (code "97") (name "Net-(R220-Pad2)") (class "Default")
      (node (ref "R220") (pin "2") (pinfunction "2_2") (pintype "passive"))
      (node (ref "U204") (pin "1") (pinfunction "RG_1") (pintype "passive"))
    )
    (net (code "98") (name "Net-(R222-Pad1)") (class "Default")
      (node (ref "R222") (pin "1") (pinfunction "1_1") (pintype "passive"))
      (node (ref "U206") (pin "8") (pinfunction "RG_8") (pintype "passive"))
    )
    (net (code "99") (name "Net-(R222-Pad2)") (class "Default")
      (node (ref "R222") (pin "2") (pinfunction "2_2") (pintype "passive"))
      (node (ref "U206") (pin "1") (pinfunction "RG_1") (pintype "passive"))
    )
    (net (code "100") (name "Net-(R305-Pad1)") (class "Default")
      (node (ref "R305") (pin "1") (pinfunction "1_1") (pintype "passive"))
      (node (ref "R307") (pin "2") (pinfunction "2_2") (pintype "passive"))
    )
    (net (code "101") (name "Net-(R305-Pad2)") (class "Default")
      (node (ref "R305") (pin "2") (pinfunction "2_2") (pintype "passive"))
      (node (ref "R306") (pin "2") (pinfunction "2_2") (pintype "passive"))
    )
    (net (code "102") (name "Net-(R306-Pad1)") (class "Default")
      (node (ref "R306") (pin "1") (pinfunction "1_1") (pintype "passive"))
      (node (ref "R308") (pin "2") (pinfunction "2_2") (pintype "passive"))
    )
    (net (code "103") (name "Net-(R307-Pad1)") (class "Default")
      (node (ref "R307") (pin "1") (pinfunction "1_1") (pintype "passive"))
      (node (ref "R309") (pin "2") (pinfunction "2_2") (pintype "passive"))
    )
    (net (code "104") (name "Net-(R311-Pad1)") (class "Default")
      (node (ref "R311") (pin "1") (pinfunction "1_1") (pintype "passive"))
      (node (ref "U304") (pin "8") (pinfunction "RG_8") (pintype "passive"))
    )
    (net (code "105") (name "Net-(R311-Pad2)") (class "Default")
      (node (ref "R311") (pin "2") (pinfunction "2_2") (pintype "passive"))
      (node (ref "U304") (pin "1") (pinfunction "RG_1") (pintype "passive"))
    )
    (net (code "106") (name "Net-(U101-C1)") (class "Default")
      (node (ref "C104") (pin "2") (pinfunction "2_2") (pintype "passive"))
      (node (ref "U101") (pin "20") (pinfunction "C1_20") (pintype "bidirectional"))
    )
    (net (code "107") (name "Net-(U101-C2)") (class "Default")
      (node (ref "C103") (pin "2") (pinfunction "2_2") (pintype "passive"))
      (node (ref "U101") (pin "21") (pinfunction "C2_21") (pintype "bidirectional"))
    )
    (net (code "108") (name "Net-(U101-FLT)") (class "Default")
      (node (ref "R103") (pin "1") (pinfunction "1_1") (pintype "passive"))
      (node (ref "U101") (pin "3") (pinfunction "FLT_3") (pintype "bidirectional"))
    )
    (net (code "109") (name "Net-(U101-VOUT)") (class "Default")
      (node (ref "U101") (pin "17") (pinfunction "VOUT_17") (pintype "bidirectional"))
      (node (ref "U102") (pin "3") (pinfunction "+_3") (pintype "input"))
    )
    (net (code "110") (name "Net-(U103-BYP)") (class "Default")
      (node (ref "C112") (pin "1") (pinfunction "1_1") (pintype "passive"))
      (node (ref "U103") (pin "4") (pinfunction "BYP_4") (pintype "power_in"))
    )
    (net (code "111") (name "Net-(U105-CH0)") (class "Default")
      (node (ref "C121") (pin "1") (pinfunction "1_1") (pintype "passive"))
      (node (ref "R123") (pin "2") (pinfunction "2_2") (pintype "passive"))
      (node (ref "U105") (pin "2") (pinfunction "CH0_2") (pintype "input"))
    )
    (net (code "112") (name "Net-(U105-CH1)") (class "Default")
      (node (ref "C118") (pin "1") (pinfunction "1_1") (pintype "passive"))
      (node (ref "R121") (pin "2") (pinfunction "2_2") (pintype "passive"))
      (node (ref "U105") (pin "3") (pinfunction "CH1_3") (pintype "input"))
    )
    (net (code "113") (name "Net-(U201-C1)") (class "Default")
      (node (ref "C202") (pin "2") (pinfunction "2_2") (pintype "passive"))
      (node (ref "U201") (pin "20") (pinfunction "C1_20") (pintype "bidirectional"))
    )
    (net (code "114") (name "Net-(U201-C2)") (class "Default")
      (node (ref "C201") (pin "2") (pinfunction "2_2") (pintype "passive"))
      (node (ref "U201") (pin "21") (pinfunction "C2_21") (pintype "bidirectional"))
    )
    (net (code "115") (name "Net-(U201-FLT)") (class "Default")
      (node (ref "R202") (pin "1") (pinfunction "1_1") (pintype "passive"))
      (node (ref "U201") (pin "3") (pinfunction "FLT_3") (pintype "bidirectional"))
    )
    (net (code "116") (name "Net-(U201-VOUT)") (class "Default")
      (node (ref "U201") (pin "17") (pinfunction "VOUT_17") (pintype "bidirectional"))
      (node (ref "U202") (pin "3") (pinfunction "+_3") (pintype "input"))
    )
    (net (code "117") (name "Net-(U203-BYP)") (class "Default")
      (node (ref "C212") (pin "1") (pinfunction "1_1") (pintype "passive"))
      (node (ref "U203") (pin "4") (pinfunction "BYP_4") (pintype "power_in"))
    )
    (net (code "118") (name "Net-(U205-CH0)") (class "Default")
      (node (ref "C221") (pin "1") (pinfunction "1_1") (pintype "passive"))
      (node (ref "R223") (pin "2") (pinfunction "2_2") (pintype "passive"))
      (node (ref "U205") (pin "2") (pinfunction "CH0_2") (pintype "input"))
    )
    (net (code "119") (name "Net-(U205-CH1)") (class "Default")
      (node (ref "C218") (pin "1") (pinfunction "1_1") (pintype "passive"))
      (node (ref "R221") (pin "2") (pinfunction "2_2") (pintype "passive"))
      (node (ref "U205") (pin "3") (pinfunction "CH1_3") (pintype "input"))
    )
    (net (code "120") (name "Net-(U301-CC+)") (class "Default")
      (node (ref "C304") (pin "2") (pinfunction "2_2") (pintype "passive"))
      (node (ref "U301") (pin "1") (pinfunction "CC+_1") (pintype "passive"))
    )
    (net (code "121") (name "Net-(U301-CC-)") (class "Default")
      (node (ref "C310") (pin "1") (pinfunction "1_1") (pintype "passive"))
      (node (ref "U301") (pin "8") (pinfunction "CC-_8") (pintype "passive"))
    )
    (net (code "122") (name "Net-(U301-SS)") (class "Default")
      (node (ref "C309") (pin "1") (pinfunction "1_1") (pintype "passive"))
      (node (ref "U301") (pin "7") (pinfunction "SS_7") (pintype "passive"))
    )
    (net (code "123") (name "Net-(U301-VREF)") (class "Default")
      (node (ref "C308") (pin "1") (pinfunction "1_1") (pintype "passive"))
      (node (ref "U301") (pin "6") (pinfunction "VREF_6") (pintype "power_in"))
    )
    (net (code "124") (name "Net-(U302-BYP)") (class "Default")
      (node (ref "C314") (pin "1") (pinfunction "1_1") (pintype "passive"))
      (node (ref "U302") (pin "4") (pinfunction "BYP_4") (pintype "power_in"))
    )
    (net (code "125") (name "Net-(U303-CB)") (class "Default")
      (node (ref "C311") (pin "1") (pinfunction "1_1") (pintype "passive"))
      (node (ref "U303") (pin "1") (pinfunction "CB_1") (pintype "output"))
    )
    (net (code "126") (name "Net-(U303-FB)") (class "Default")
      (node (ref "R303") (pin "1") (pinfunction "1_1") (pintype "passive"))
      (node (ref "R304") (pin "2") (pinfunction "2_2") (pintype "passive"))
      (node (ref "U303") (pin "4") (pinfunction "FB_4") (pintype "input"))
    )
    (net (code "127") (name "Net-(U304-+)") (class "Default")
      (node (ref "R308") (pin "1") (pinfunction "1_1") (pintype "passive"))
      (node (ref "R310") (pin "2") (pinfunction "2_2") (pintype "passive"))
      (node (ref "U304") (pin "3") (pinfunction "+_3") (pintype "input"))
    )
    (net (code "128") (name "Net-(U304--)") (class "Default")
      (node (ref "R313") (pin "2") (pinfunction "2_2") (pintype "passive"))
      (node (ref "U304") (pin "2") (pinfunction "-_2") (pintype "input"))
    )
    (net (code "129") (name "Net-(U305-CH0)") (class "Default")
      (node (ref "R314") (pin "2") (pinfunction "2_2") (pintype "passive"))
      (node (ref "U305") (pin "2") (pinfunction "CH0_2") (pintype "input"))
    )
    (net (code "130") (name "Net-(U305-CH1)") (class "Default")
      (node (ref "C323") (pin "1") (pinfunction "1_1") (pintype "passive"))
      (node (ref "R312") (pin "2") (pinfunction "2_2") (pintype "passive"))
      (node (ref "U305") (pin "3") (pinfunction "CH1_3") (pintype "input"))
    )
    (net (code "131") (name "SCK") (class "Default")
      (node (ref "C411") (pin "1") (pinfunction "1_1") (pintype "passive"))
      (node (ref "R411") (pin "1") (pinfunction "1_1") (pintype "passive"))
      (node (ref "U101") (pin "8") (pinfunction "SCK_8") (pintype "bidirectional"))
      (node (ref "U105") (pin "7") (pinfunction "SCK_7") (pintype "input"))
      (node (ref "U201") (pin "8") (pinfunction "SCK_8") (pintype "bidirectional"))
      (node (ref "U205") (pin "7") (pinfunction "SCK_7") (pintype "input"))
      (node (ref "U305") (pin "7") (pinfunction "SCK_7") (pintype "input"))
      (node (ref "U403") (pin "7") (pinfunction "VO1_7") (pintype "output"))
    )
    (net (code "132") (name "SCK_I") (class "Default")
      (node (ref "JP301") (pin "3") (pinfunction "3_3") (pintype "passive"))
      (node (ref "Q405") (pin "1") (pinfunction "B_1") (pintype "passive"))
    )
    (net (code "133") (name "SDO_DAC2") (class "Default")
      (node (ref "U101") (pin "9") (pinfunction "SDI_9") (pintype "bidirectional"))
      (node (ref "U201") (pin "10") (pinfunction "SDO_10") (pintype "bidirectional"))
    )
    (net (code "134") (name "VREF1") (class "Default")
      (node (ref "C108") (pin "1") (pinfunction "1_1") (pintype "passive"))
      (node (ref "U101") (pin "14") (pinfunction "REF_OUT_14") (pintype "bidirectional"))
      (node (ref "U101") (pin "15") (pinfunction "REF_IN_15") (pintype "bidirectional"))
      (node (ref "U103") (pin "1") (pinfunction "VIN_1") (pintype "power_in"))
      (node (ref "U103") (pin "3") (pinfunction "ON/OFF_3") (pintype "input"))
    )
    (net (code "135") (name "VREF2") (class "Default")
      (node (ref "C210") (pin "1") (pinfunction "1_1") (pintype "passive"))
      (node (ref "U201") (pin "14") (pinfunction "REF_OUT_14") (pintype "bidirectional"))
      (node (ref "U201") (pin "15") (pinfunction "REF_IN_15") (pintype "bidirectional"))
      (node (ref "U203") (pin "1") (pinfunction "VIN_1") (pintype "power_in"))
      (node (ref "U203") (pin "3") (pinfunction "ON/OFF_3") (pintype "input"))
    )
    (net (code "136") (name "VSENSE+") (class "Default")
      (node (ref "PAD301") (pin "1") (pinfunction "P_1") (pintype "passive"))
      (node (ref "R309") (pin "1") (pinfunction "1_1") (pintype "passive"))
    )
    (net (code "137") (name "VSENSE-") (class "Default")
      (node (ref "PAD302") (pin "1") (pinfunction "P_1") (pintype "passive"))
      (node (ref "R310") (pin "1") (pinfunction "1_1") (pintype "passive"))
      (node (ref "R313") (pin "1") (pinfunction "1_1") (pintype "passive"))
    )
    (net (code "138") (name "unconnected-(J301-Pad2)") (class "Default")
      (node (ref "J301") (pin "2") (pinfunction "2_2") (pintype "passive"))
    )
    (net (code "139") (name "unconnected-(U101-BST-Pad19)") (class "Default")
      (node (ref "U101") (pin "19") (pinfunction "BST_19") (pintype "bidirectional"))
    )
    (net (code "140") (name "unconnected-(U101-IOUT-Pad18)") (class "Default")
      (node (ref "U101") (pin "18") (pinfunction "IOUT_18") (pintype "bidirectional"))
    )
    (net (code "141") (name "unconnected-(U101-O_TRIM-Pad16)") (class "Default")
      (node (ref "U101") (pin "16") (pinfunction "O_TRIM_16") (pintype "bidirectional"))
    )
    (net (code "142") (name "unconnected-(U101-SDO-Pad10)") (class "Default")
      (node (ref "U101") (pin "10") (pinfunction "SDO_10") (pintype "bidirectional"))
    )
    (net (code "143") (name "unconnected-(U201-BST-Pad19)") (class "Default")
      (node (ref "U201") (pin "19") (pinfunction "BST_19") (pintype "bidirectional"))
    )
    (net (code "144") (name "unconnected-(U201-IOUT-Pad18)") (class "Default")
      (node (ref "U201") (pin "18") (pinfunction "IOUT_18") (pintype "bidirectional"))
    )
    (net (code "145") (name "unconnected-(U201-O_TRIM-Pad16)") (class "Default")
      (node (ref "U201") (pin "16") (pinfunction "O_TRIM_16") (pintype "bidirectional"))
    )
    (net (code "146") (name "unconnected-(U303-ON{slash}~{OFF}-Pad5)") (class "Default")
      (node (ref "U303") (pin "5") (pinfunction "ON/~{OFF}_5") (pintype "input"))
    )
    (net (code "147") (name "unconnected-(U303-SS-Pad2)") (class "Default")
      (node (ref "U303") (pin "2") (pinfunction "SS_2") (pintype "input"))
    )
    (net (code "148") (name "unconnected-(U303-SYNC-Pad3)") (class "Default")
      (node (ref "U303") (pin "3") (pinfunction "SYNC_3") (pintype "bidirectional"))
    )
  )
)
